# PSPS_AVNC_SRD_fullBoard-2020-09-15.net
KiCad netlist of a schematic drawn in EAGLE
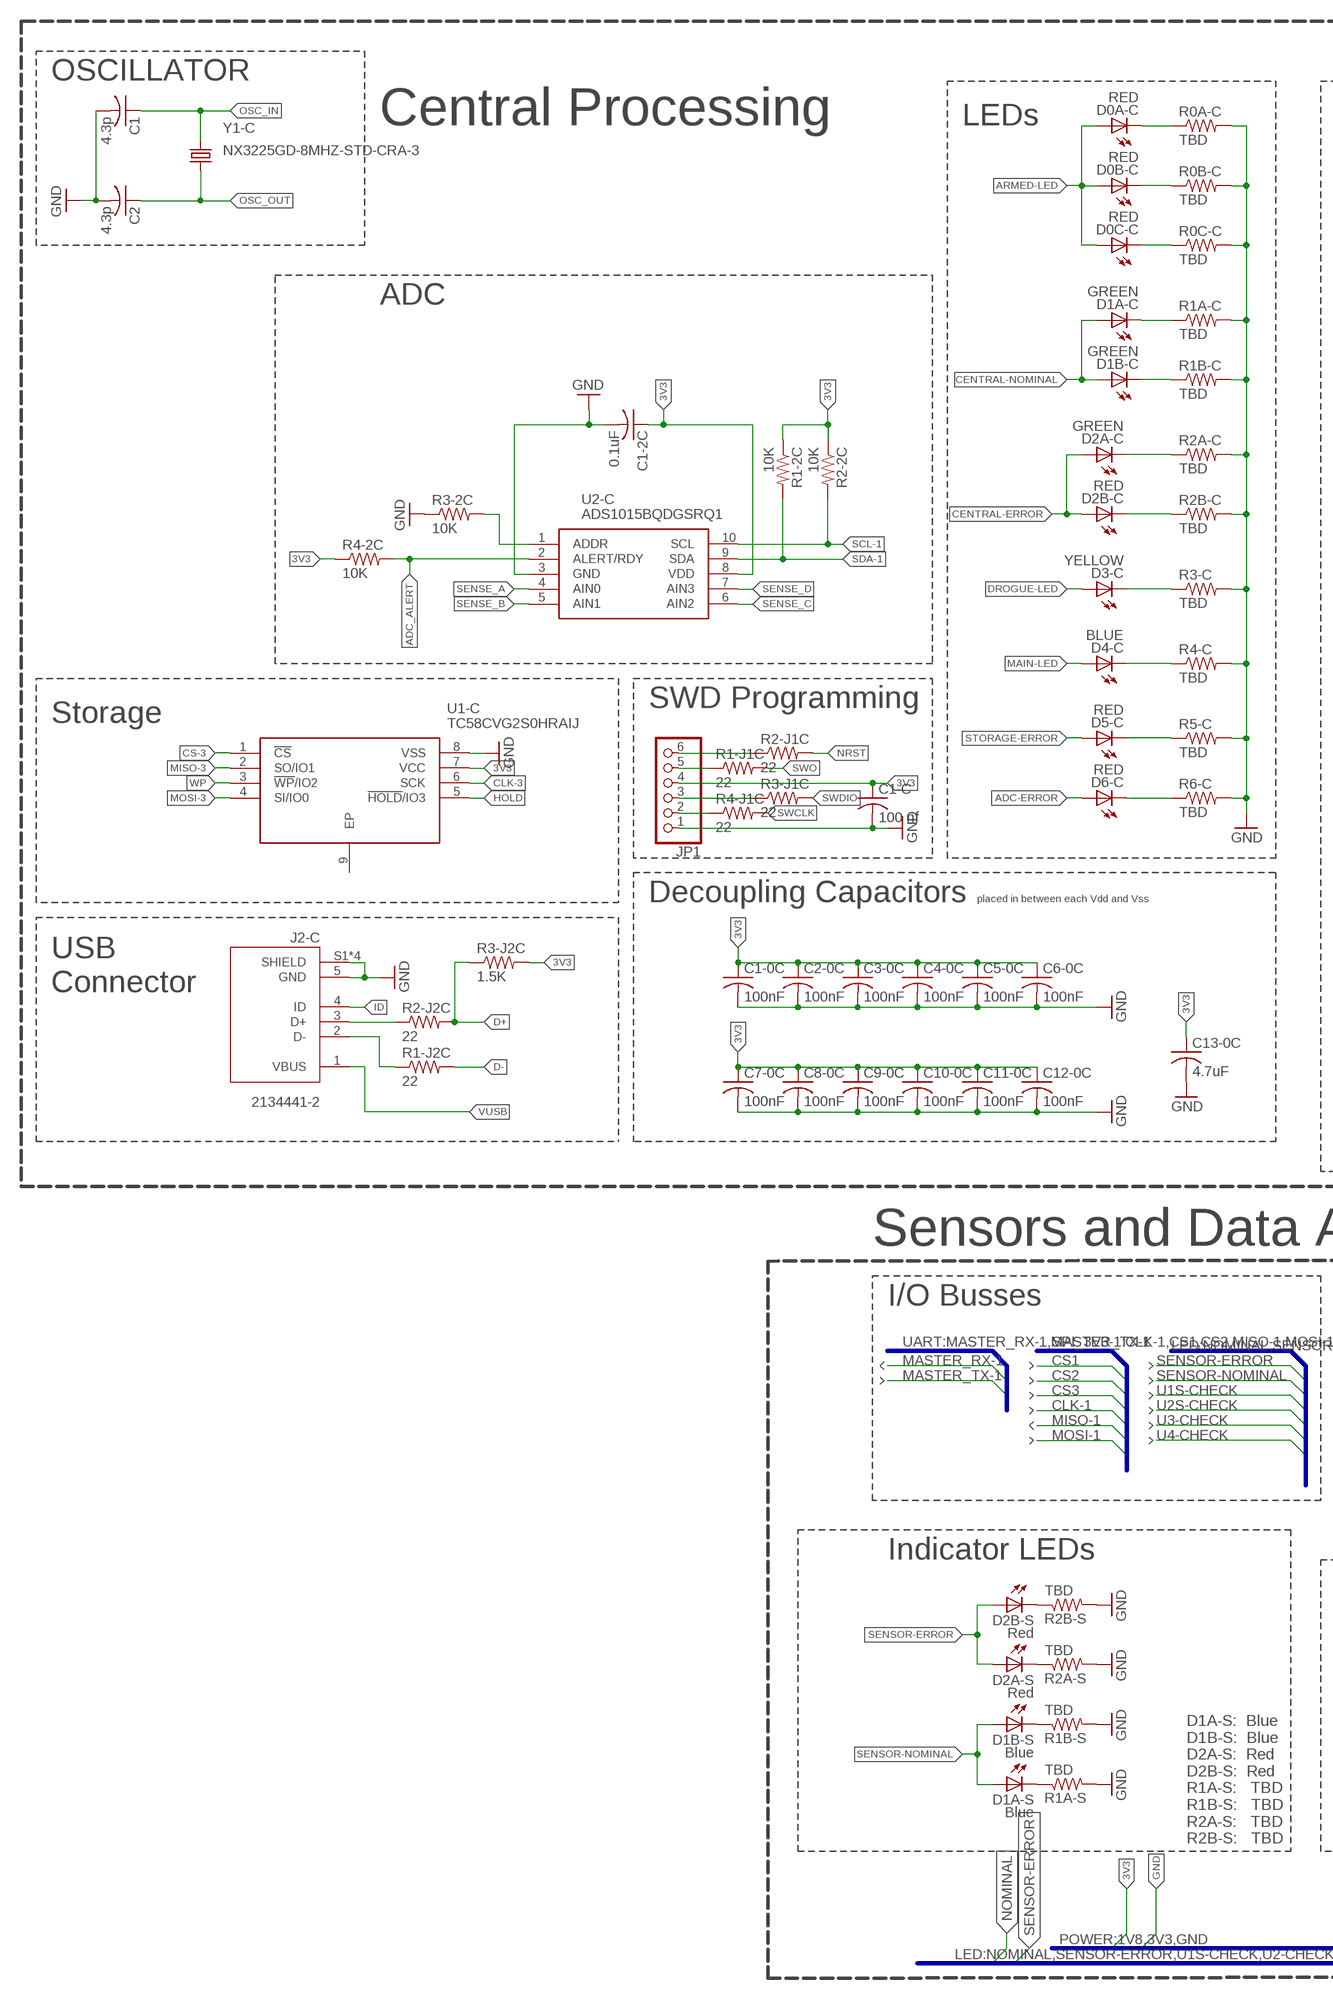
[diagram p0: schematic, sheet 1, part 1 of 3]
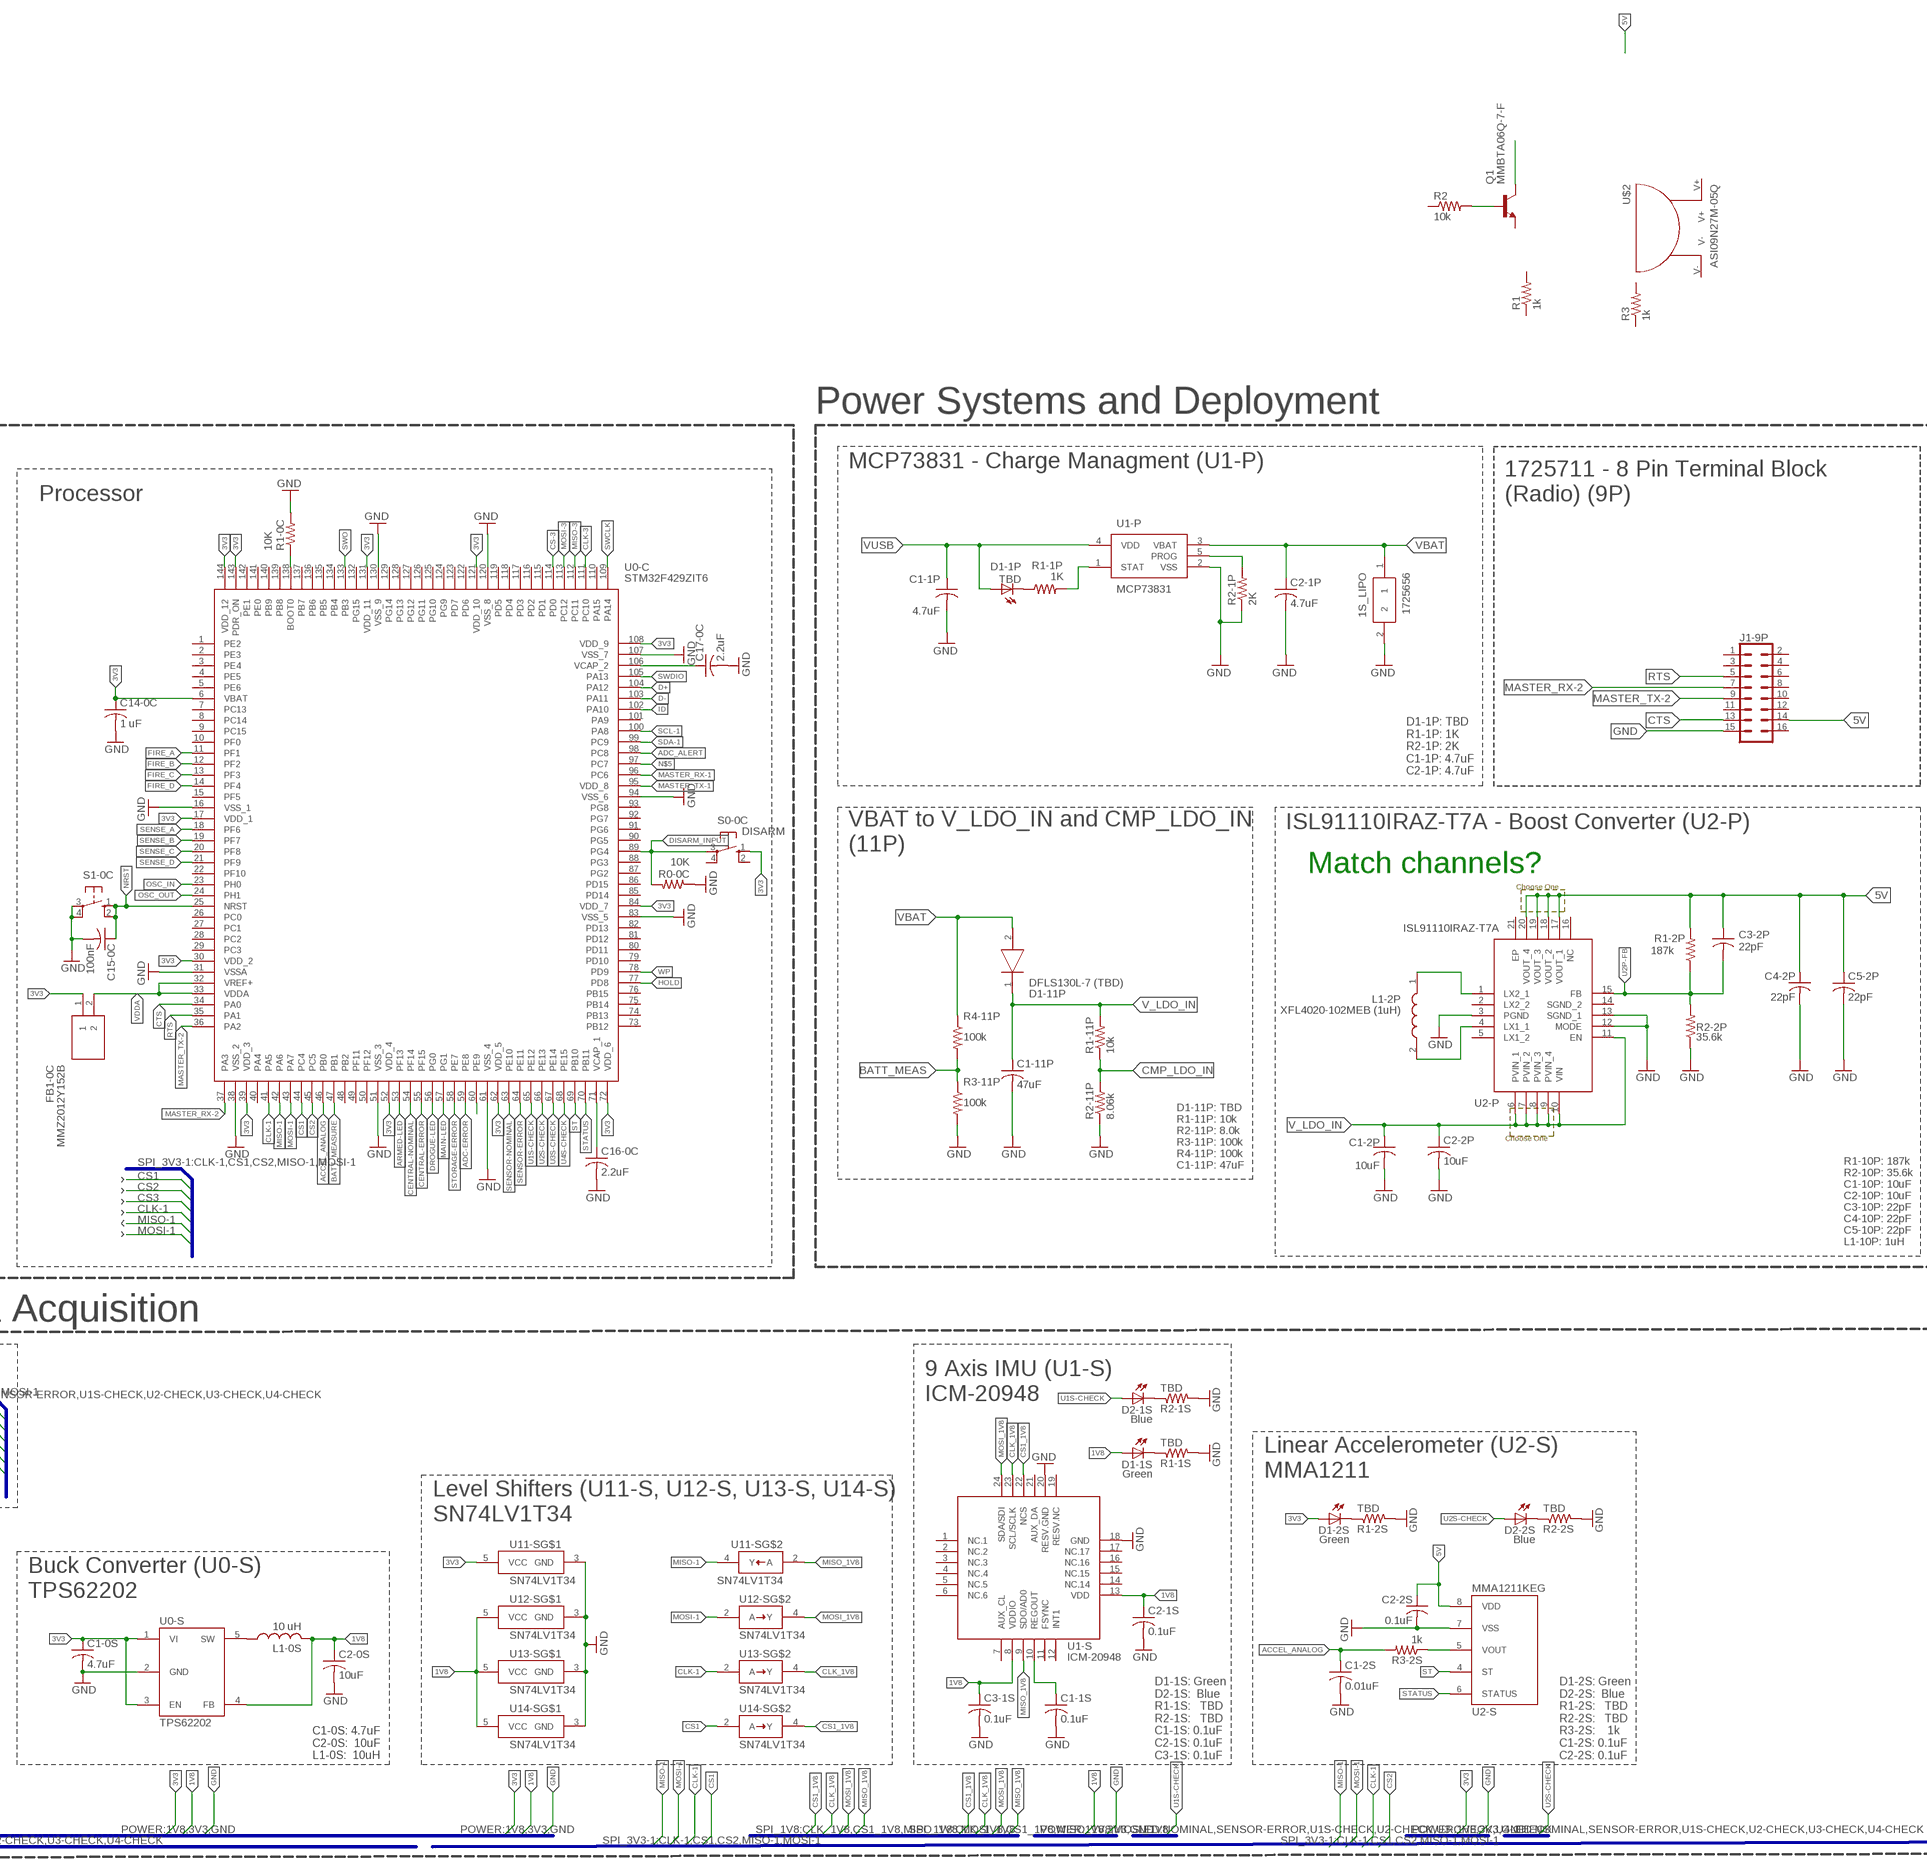
[diagram p1: schematic, sheet 1, part 2 of 3]
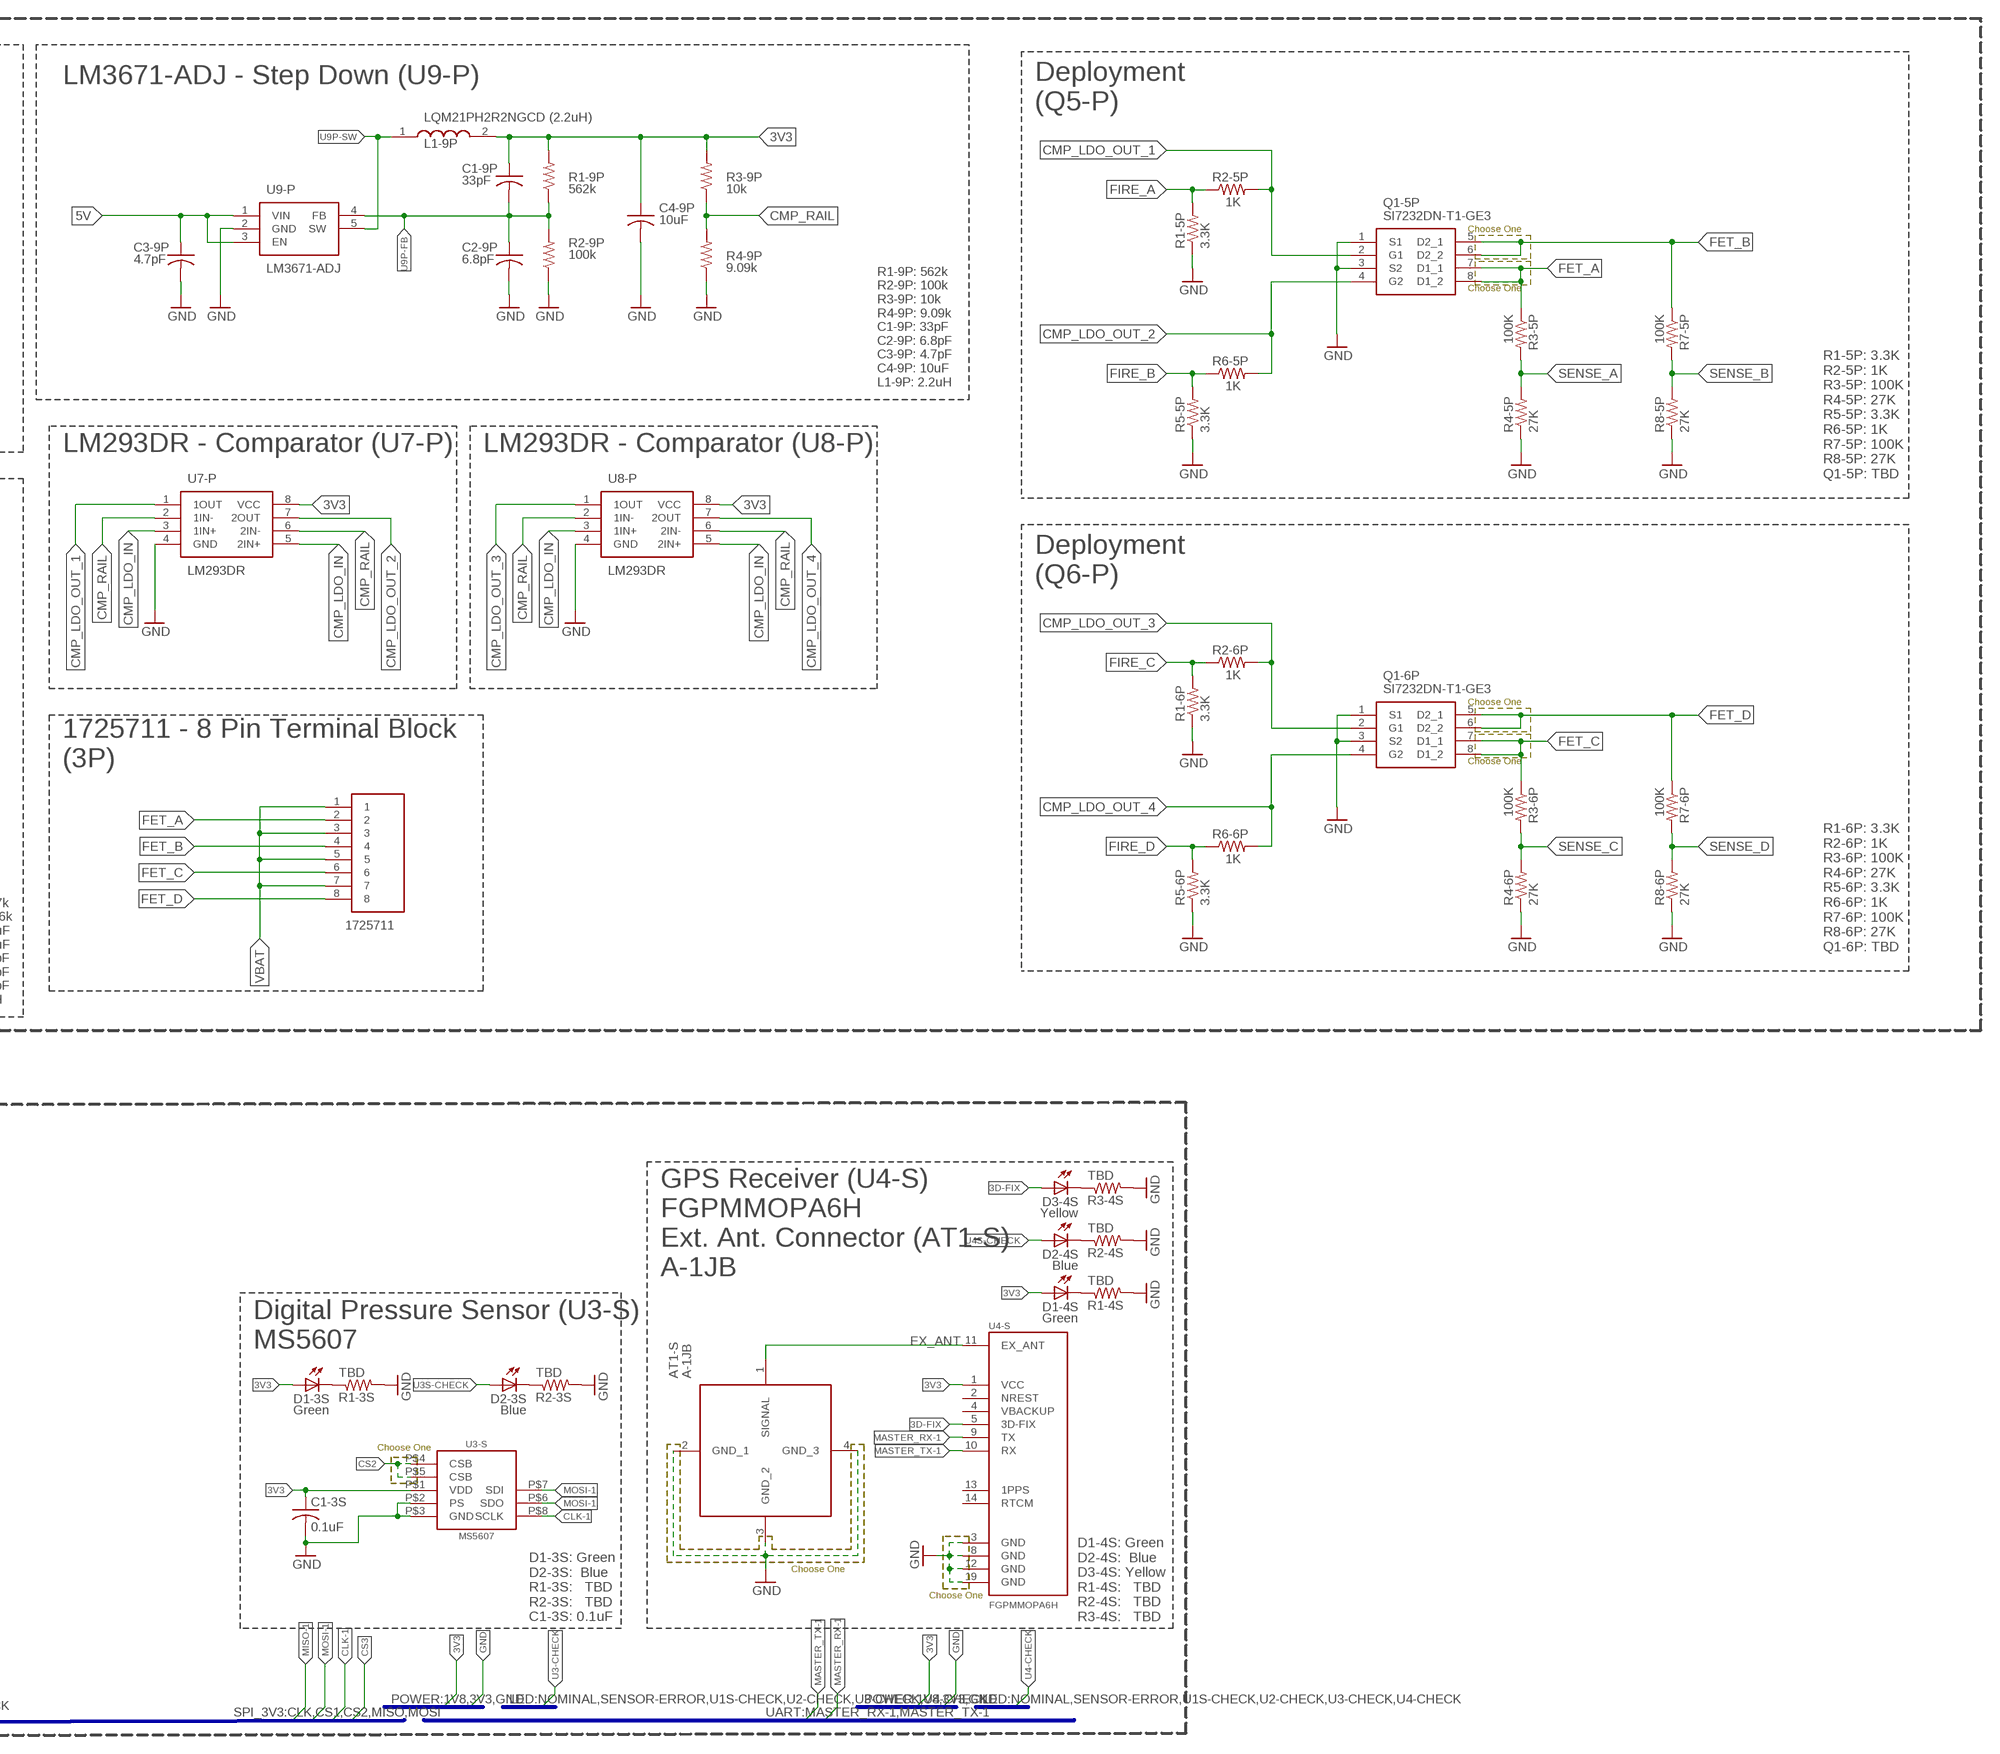
[diagram p2: schematic, sheet 1, part 3 of 3]

(export (version "E")
  (design (tool "Eeschema 10.0.6"))
  (components
    (comp (ref "1S_LIPO")
      (value "1725656")
      (footprint "eagle-import:1725656")
      (fields (field (name "MOUSER_PART_NUMBER") "651-1725656"))
      (libsource (lib "eagle-import") (part "1725656"))
    )
    (comp (ref "AT1-S")
      (value "A-1JB")
      (footprint "eagle-import:A1JB")
      (fields (field (name "MOUSER_PART_NUMBER") "523-A-1JB"))
      (libsource (lib "eagle-import") (part "A-1JB"))
    )
    (comp (ref "C1")
      (value "4.3p")
      (footprint "eagle-import:C0805")
      (libsource (lib "eagle-import") (part "rcl_334_C-USC0805"))
    )
    (comp (ref "C1-0C")
      (value "100nF")
      (footprint "eagle-import:C0805")
      (libsource (lib "eagle-import") (part "rcl_334_C-USC0805"))
    )
    (comp (ref "C1-0S")
      (value "4.7uF")
      (footprint "eagle-import:C0805")
      (libsource (lib "eagle-import") (part "resistor_348_C-USC0805"))
    )
    (comp (ref "C1-1P")
      (value "4.7uF")
      (footprint "eagle-import:C0805")
      (libsource (lib "eagle-import") (part "resistor_348_C-USC0805"))
    )
    (comp (ref "C1-1S")
      (value "0.1uF")
      (footprint "eagle-import:C0805")
      (libsource (lib "eagle-import") (part "resistor_348_C-USC0805"))
    )
    (comp (ref "C1-2C")
      (value "0.1uF")
      (footprint "eagle-import:C0805")
      (libsource (lib "eagle-import") (part "rcl_334_C-USC0805"))
    )
    (comp (ref "C1-2P")
      (value "10uF")
      (footprint "eagle-import:C0805")
      (libsource (lib "eagle-import") (part "resistor_348_C-USC0805"))
    )
    (comp (ref "C1-2S")
      (value "0.01uF")
      (footprint "eagle-import:C0805")
      (libsource (lib "eagle-import") (part "resistor_348_C-USC0805"))
    )
    (comp (ref "C1-3S")
      (value "0.1uF")
      (footprint "eagle-import:C0805")
      (libsource (lib "eagle-import") (part "resistor_348_C-USC0805"))
    )
    (comp (ref "C1-9P")
      (value "33pF")
      (footprint "eagle-import:C0805")
      (libsource (lib "eagle-import") (part "resistor_348_C-USC0805"))
    )
    (comp (ref "C1-11P")
      (value "47uF")
      (footprint "eagle-import:C0805")
      (libsource (lib "eagle-import") (part "resistor_348_C-USC0805"))
    )
    (comp (ref "C1-C")
      (value "100 nf")
      (footprint "eagle-import:C0805")
      (libsource (lib "eagle-import") (part "rcl_334_C-USC0805"))
    )
    (comp (ref "C2")
      (value "4.3p")
      (footprint "eagle-import:C0805")
      (libsource (lib "eagle-import") (part "rcl_334_C-USC0805"))
    )
    (comp (ref "C2-0C")
      (value "100nF")
      (footprint "eagle-import:C0805")
      (libsource (lib "eagle-import") (part "rcl_334_C-USC0805"))
    )
    (comp (ref "C2-0S")
      (value "10uF")
      (footprint "eagle-import:C0805")
      (libsource (lib "eagle-import") (part "resistor_348_C-USC0805"))
    )
    (comp (ref "C2-1P")
      (value "4.7uF")
      (footprint "eagle-import:C0805")
      (libsource (lib "eagle-import") (part "resistor_348_C-USC0805"))
    )
    (comp (ref "C2-1S")
      (value "0.1uF")
      (footprint "eagle-import:C0805")
      (libsource (lib "eagle-import") (part "resistor_348_C-USC0805"))
    )
    (comp (ref "C2-2P")
      (value "10uF")
      (footprint "eagle-import:C0805")
      (libsource (lib "eagle-import") (part "C-USC0805"))
    )
    (comp (ref "C2-2S")
      (value "0.1uF")
      (footprint "eagle-import:C0805")
      (libsource (lib "eagle-import") (part "resistor_348_C-USC0805"))
    )
    (comp (ref "C2-9P")
      (value "6.8pF")
      (footprint "eagle-import:C0805")
      (libsource (lib "eagle-import") (part "resistor_348_C-USC0805"))
    )
    (comp (ref "C3-0C")
      (value "100nF")
      (footprint "eagle-import:C0805")
      (libsource (lib "eagle-import") (part "rcl_334_C-USC0805"))
    )
    (comp (ref "C3-1S")
      (value "0.1uF")
      (footprint "eagle-import:C0805")
      (libsource (lib "eagle-import") (part "resistor_348_C-USC0805"))
    )
    (comp (ref "C3-2P")
      (value "22pF")
      (footprint "eagle-import:C0805")
      (libsource (lib "eagle-import") (part "resistor_348_C-USC0805"))
    )
    (comp (ref "C3-9P")
      (value "4.7pF")
      (footprint "eagle-import:C0805")
      (libsource (lib "eagle-import") (part "resistor_348_C-USC0805"))
    )
    (comp (ref "C4-0C")
      (value "100nF")
      (footprint "eagle-import:C0805")
      (libsource (lib "eagle-import") (part "rcl_334_C-USC0805"))
    )
    (comp (ref "C4-2P")
      (value "22pF")
      (footprint "eagle-import:C0805")
      (fields (field (name "SPICEPREFIX") "C"))
      (libsource (lib "eagle-import") (part "resistor_348_C-USC0805"))
    )
    (comp (ref "C4-9P")
      (value "10uF")
      (footprint "eagle-import:C0805")
      (libsource (lib "eagle-import") (part "resistor_348_C-USC0805"))
    )
    (comp (ref "C5-0C")
      (value "100nF")
      (footprint "eagle-import:C0805")
      (libsource (lib "eagle-import") (part "rcl_334_C-USC0805"))
    )
    (comp (ref "C5-2P")
      (value "22pF")
      (footprint "eagle-import:C0805")
      (libsource (lib "eagle-import") (part "C-USC0805"))
    )
    (comp (ref "C6-0C")
      (value "100nF")
      (footprint "eagle-import:C0805")
      (libsource (lib "eagle-import") (part "rcl_334_C-USC0805"))
    )
    (comp (ref "C7-0C")
      (value "100nF")
      (footprint "eagle-import:C0805")
      (libsource (lib "eagle-import") (part "rcl_334_C-USC0805"))
    )
    (comp (ref "C8-0C")
      (value "100nF")
      (footprint "eagle-import:C0805")
      (libsource (lib "eagle-import") (part "rcl_334_C-USC0805"))
    )
    (comp (ref "C9-0C")
      (value "100nF")
      (footprint "eagle-import:C0805")
      (libsource (lib "eagle-import") (part "rcl_334_C-USC0805"))
    )
    (comp (ref "C10-0C")
      (value "100nF")
      (footprint "eagle-import:C0805")
      (libsource (lib "eagle-import") (part "rcl_334_C-USC0805"))
    )
    (comp (ref "C11-0C")
      (value "100nF")
      (footprint "eagle-import:C0805")
      (libsource (lib "eagle-import") (part "rcl_334_C-USC0805"))
    )
    (comp (ref "C12-0C")
      (value "100nF")
      (footprint "eagle-import:C0805")
      (libsource (lib "eagle-import") (part "rcl_334_C-USC0805"))
    )
    (comp (ref "C13-0C")
      (value "4.7uF")
      (footprint "eagle-import:C0805")
      (libsource (lib "eagle-import") (part "rcl_334_C-USC0805"))
    )
    (comp (ref "C14-0C")
      (value "1 uF")
      (footprint "eagle-import:C0805")
      (libsource (lib "eagle-import") (part "rcl_334_C-USC0805"))
    )
    (comp (ref "C15-0C")
      (value "100nF")
      (footprint "eagle-import:C0805")
      (libsource (lib "eagle-import") (part "rcl_334_C-USC0805"))
    )
    (comp (ref "C16-0C")
      (value "2.2uF")
      (footprint "eagle-import:C0805")
      (libsource (lib "eagle-import") (part "rcl_334_C-USC0805"))
    )
    (comp (ref "C17-0C")
      (value "2.2uF")
      (footprint "eagle-import:C0805")
      (libsource (lib "eagle-import") (part "rcl_334_C-USC0805"))
    )
    (comp (ref "D0A-C")
      (value "RED")
      (footprint "eagle-import:CHIPLED_0805")
      (libsource (lib "eagle-import") (part "adafruit_420_LEDCHIPLED_0805"))
    )
    (comp (ref "D0B-C")
      (value "RED")
      (footprint "eagle-import:CHIPLED_0805")
      (libsource (lib "eagle-import") (part "adafruit_420_LEDCHIPLED_0805"))
    )
    (comp (ref "D0C-C")
      (value "RED")
      (footprint "eagle-import:CHIPLED_0805")
      (libsource (lib "eagle-import") (part "adafruit_420_LEDCHIPLED_0805"))
    )
    (comp (ref "D1-1P")
      (value "TBD")
      (footprint "eagle-import:CHIPLED_0805")
      (libsource (lib "eagle-import") (part "adafruit_420_LEDCHIPLED_0805"))
    )
    (comp (ref "D1-1S")
      (value "Green")
      (footprint "eagle-import:CHIPLED_0805")
      (libsource (lib "eagle-import") (part "LEDCHIPLED_0805"))
    )
    (comp (ref "D1-2S")
      (value "Green")
      (footprint "eagle-import:CHIPLED_0805")
      (libsource (lib "eagle-import") (part "LEDCHIPLED_0805"))
    )
    (comp (ref "D1-3S")
      (value "Green")
      (footprint "eagle-import:CHIPLED_0805")
      (libsource (lib "eagle-import") (part "LEDCHIPLED_0805"))
    )
    (comp (ref "D1-4S")
      (value "Green")
      (footprint "eagle-import:CHIPLED_0805")
      (libsource (lib "eagle-import") (part "LEDCHIPLED_0805"))
    )
    (comp (ref "D1-11P")
      (value "DFLS130L-7 (TBD)")
      (footprint "eagle-import:POWERDI_123")
      (fields
        (field (name "MANUFACTURER_PART_NUMBER") "DFLS130L-7")
        (field (name "MOUSER_PART_NUMBER") "621-DFLS130L")
      )
      (libsource (lib "eagle-import") (part "DFLS130L-7"))
    )
    (comp (ref "D1A-C")
      (value "GREEN")
      (footprint "eagle-import:CHIPLED_0805")
      (libsource (lib "eagle-import") (part "adafruit_420_LEDCHIPLED_0805"))
    )
    (comp (ref "D1A-S")
      (value "Blue")
      (footprint "eagle-import:CHIPLED_0805")
      (libsource (lib "eagle-import") (part "LEDCHIPLED_0805"))
    )
    (comp (ref "D1B-C")
      (value "GREEN")
      (footprint "eagle-import:CHIPLED_0805")
      (libsource (lib "eagle-import") (part "adafruit_420_LEDCHIPLED_0805"))
    )
    (comp (ref "D1B-S")
      (value "Blue")
      (footprint "eagle-import:CHIPLED_0805")
      (libsource (lib "eagle-import") (part "LEDCHIPLED_0805"))
    )
    (comp (ref "D2-1S")
      (value "Blue")
      (footprint "eagle-import:CHIPLED_0805")
      (libsource (lib "eagle-import") (part "LEDCHIPLED_0805"))
    )
    (comp (ref "D2-2S")
      (value "Blue")
      (footprint "eagle-import:CHIPLED_0805")
      (libsource (lib "eagle-import") (part "LEDCHIPLED_0805"))
    )
    (comp (ref "D2-3S")
      (value "Blue")
      (footprint "eagle-import:CHIPLED_0805")
      (libsource (lib "eagle-import") (part "LEDCHIPLED_0805"))
    )
    (comp (ref "D2-4S")
      (value "Blue")
      (footprint "eagle-import:CHIPLED_0805")
      (libsource (lib "eagle-import") (part "LEDCHIPLED_0805"))
    )
    (comp (ref "D2A-C")
      (value "GREEN")
      (footprint "eagle-import:CHIPLED_0805")
      (libsource (lib "eagle-import") (part "adafruit_420_LEDCHIPLED_0805"))
    )
    (comp (ref "D2A-S")
      (value "Red")
      (footprint "eagle-import:CHIPLED_0805")
      (libsource (lib "eagle-import") (part "LEDCHIPLED_0805"))
    )
    (comp (ref "D2B-C")
      (value "RED")
      (footprint "eagle-import:CHIPLED_0805")
      (libsource (lib "eagle-import") (part "adafruit_420_LEDCHIPLED_0805"))
    )
    (comp (ref "D2B-S")
      (value "Red")
      (footprint "eagle-import:CHIPLED_0805")
      (libsource (lib "eagle-import") (part "LEDCHIPLED_0805"))
    )
    (comp (ref "D3-4S")
      (value "Yellow")
      (footprint "eagle-import:CHIPLED_0805")
      (libsource (lib "eagle-import") (part "LEDCHIPLED_0805"))
    )
    (comp (ref "D3-C")
      (value "YELLOW")
      (footprint "eagle-import:CHIPLED_0805")
      (libsource (lib "eagle-import") (part "adafruit_420_LEDCHIPLED_0805"))
    )
    (comp (ref "D4-C")
      (value "BLUE")
      (footprint "eagle-import:CHIPLED_0805")
      (libsource (lib "eagle-import") (part "adafruit_420_LEDCHIPLED_0805"))
    )
    (comp (ref "D5-C")
      (value "RED")
      (footprint "eagle-import:CHIPLED_0805")
      (libsource (lib "eagle-import") (part "adafruit_420_LEDCHIPLED_0805"))
    )
    (comp (ref "D6-C")
      (value "RED")
      (footprint "eagle-import:CHIPLED_0805")
      (libsource (lib "eagle-import") (part "adafruit_420_LEDCHIPLED_0805"))
    )
    (comp (ref "FB1-0C")
      (value "MMZ2012Y152B")
      (footprint "eagle-import:BEADC2012X105N")
      (fields (field (name "MOUSER_PART_NUMBER") "810-MMZ2012Y152B"))
      (libsource (lib "eagle-import") (part "MMZ2012Y152B"))
    )
    (comp (ref "J1-9P")
      (value "CONN_08X2")
      (footprint "eagle-import:2X8")
      (libsource (lib "eagle-import") (part "CONN_08X2"))
    )
    (comp (ref "J2-C")
      (value "2134441-2")
      (footprint "eagle-import:TE_2134441-2")
      (fields (field (name "DIGI-KEY_PART_NUMBER") "A118104CT-ND") (field (name "MF") "TE Connectivity"))
      (libsource (lib "eagle-import") (part "2134441-2"))
    )
    (comp (ref "J2-CHARGETERMINAL")
      (value "1725711")
      (footprint "eagle-import:1725711")
      (fields (field (name "MOUSER_PART_NUMBER") "651-1725711"))
      (libsource (lib "eagle-import") (part "1725711"))
    )
    (comp (ref "JP1")
      (value "PINHD-1X6")
      (footprint "eagle-import:1X06")
      (libsource (lib "eagle-import") (part "PINHD-1X6"))
    )
    (comp (ref "L1-0S")
      (value "10 uH")
      (footprint "eagle-import:PF0560NL")
      (libsource (lib "eagle-import") (part "PF0560.103NLT"))
    )
    (comp (ref "L1-2P")
      (value "XFL4020-102MEB (1uH)")
      (footprint "eagle-import:XFL4020")
      (fields
        (field (name "MANUFACTURER_PART_NUMBER") "XFL4020-102MEB")
        (field (name "MOUSER_PART_NUMBER") "994-XFL4020-102MEB")
      )
      (libsource (lib "eagle-import") (part "XFL4020-102MEB"))
    )
    (comp (ref "L1-9P")
      (value "LQM21PH2R2NGCD (2.2uH)")
      (footprint "eagle-import:INDC2012X100N")
      (fields
        (field (name "MANUFACTURER_PART_NUMBER") "LQM21PH2R2NGCD")
        (field (name "MOUSER_PART_NUMBER") "81-LQM21PH2R2NGCD")
      )
      (libsource (lib "eagle-import") (part "LQM21PH2R2NGCD"))
    )
    (comp (ref "Q1")
      (value "MMBTA06Q-7-F")
      (footprint "eagle-import:SOT23")
      (libsource (lib "eagle-import") (part "NPN_TRANSISTOR"))
    )
    (comp (ref "Q1-5P")
      (value "SI7232DN-T1-GE3")
      (footprint "eagle-import:POWERPAK-1212-8")
      (fields (field (name "MOUSER_PART_NUMBER") "781-SI7232DN-GE3"))
      (libsource (lib "eagle-import") (part "SI7232DN-T1-GE3"))
    )
    (comp (ref "Q1-6P")
      (value "SI7232DN-T1-GE3")
      (footprint "eagle-import:POWERPAK-1212-8")
      (fields (field (name "MOUSER_PART_NUMBER") "781-SI7232DN-GE3"))
      (libsource (lib "eagle-import") (part "SI7232DN-T1-GE3"))
    )
    (comp (ref "R0-0C")
      (value "10K")
      (footprint "eagle-import:R0805")
      (libsource (lib "eagle-import") (part "rcl_334_R-US_R0805"))
    )
    (comp (ref "R0A-C")
      (value "TBD")
      (footprint "eagle-import:M0805")
      (libsource (lib "eagle-import") (part "rcl_334_R-US_M0805"))
    )
    (comp (ref "R0B-C")
      (value "TBD")
      (footprint "eagle-import:M0805")
      (libsource (lib "eagle-import") (part "rcl_334_R-US_M0805"))
    )
    (comp (ref "R0C-C")
      (value "TBD")
      (footprint "eagle-import:M0805")
      (libsource (lib "eagle-import") (part "rcl_334_R-US_M0805"))
    )
    (comp (ref "R1")
      (value "1k")
      (footprint "eagle-import:R0805")
      (libsource (lib "eagle-import") (part "resistor_348_R-US_R0805"))
    )
    (comp (ref "R1-0C")
      (value "10K")
      (footprint "eagle-import:R0805")
      (libsource (lib "eagle-import") (part "rcl_334_R-US_R0805"))
    )
    (comp (ref "R1-1P")
      (value "1K")
      (footprint "eagle-import:R0805")
      (libsource (lib "eagle-import") (part "resistor_348_R-US_R0805"))
    )
    (comp (ref "R1-1S")
      (value "TBD")
      (footprint "eagle-import:R0805")
      (libsource (lib "eagle-import") (part "resistor_348_R-US_R0805"))
    )
    (comp (ref "R1-2C")
      (value "10K")
      (footprint "eagle-import:R0805")
      (libsource (lib "eagle-import") (part "rcl_334_R-US_R0805"))
    )
    (comp (ref "R1-2P")
      (value "187k")
      (footprint "eagle-import:R0805")
      (libsource (lib "eagle-import") (part "resistor_348_R-US_R0805"))
    )
    (comp (ref "R1-2S")
      (value "TBD")
      (footprint "eagle-import:R0805")
      (libsource (lib "eagle-import") (part "resistor_348_R-US_R0805"))
    )
    (comp (ref "R1-3S")
      (value "TBD")
      (footprint "eagle-import:R0805")
      (libsource (lib "eagle-import") (part "resistor_348_R-US_R0805"))
    )
    (comp (ref "R1-4S")
      (value "TBD")
      (footprint "eagle-import:R0805")
      (libsource (lib "eagle-import") (part "resistor_348_R-US_R0805"))
    )
    (comp (ref "R1-5P")
      (value "3.3K")
      (footprint "eagle-import:M0805")
      (libsource (lib "eagle-import") (part "rcl_334_R-US_M0805"))
    )
    (comp (ref "R1-6P")
      (value "3.3K")
      (footprint "eagle-import:M0805")
      (libsource (lib "eagle-import") (part "rcl_334_R-US_M0805"))
    )
    (comp (ref "R1-9P")
      (value "562k")
      (footprint "eagle-import:R0805")
      (libsource (lib "eagle-import") (part "resistor_348_R-US_R0805"))
    )
    (comp (ref "R1-11P")
      (value "10k")
      (footprint "eagle-import:R0805")
      (libsource (lib "eagle-import") (part "resistor_348_R-US_R0805"))
    )
    (comp (ref "R1-J1C")
      (value "22")
      (footprint "eagle-import:M0805")
      (libsource (lib "eagle-import") (part "rcl_334_R-US_M0805"))
    )
    (comp (ref "R1-J2C")
      (value "22")
      (footprint "eagle-import:M0805")
      (libsource (lib "eagle-import") (part "rcl_334_R-US_M0805"))
    )
    (comp (ref "R1A-C")
      (value "TBD")
      (footprint "eagle-import:M0805")
      (libsource (lib "eagle-import") (part "rcl_334_R-US_M0805"))
    )
    (comp (ref "R1A-S")
      (value "TBD")
      (footprint "eagle-import:R0805")
      (libsource (lib "eagle-import") (part "resistor_348_R-US_R0805"))
    )
    (comp (ref "R1B-C")
      (value "TBD")
      (footprint "eagle-import:M0805")
      (libsource (lib "eagle-import") (part "rcl_334_R-US_M0805"))
    )
    (comp (ref "R1B-S")
      (value "TBD")
      (footprint "eagle-import:R0805")
      (libsource (lib "eagle-import") (part "resistor_348_R-US_R0805"))
    )
    (comp (ref "R2")
      (value "10k")
      (footprint "eagle-import:R0805")
      (libsource (lib "eagle-import") (part "resistor_348_R-US_R0805"))
    )
    (comp (ref "R2-1P")
      (value "2K")
      (footprint "eagle-import:R0805")
      (libsource (lib "eagle-import") (part "resistor_348_R-US_R0805"))
    )
    (comp (ref "R2-1S")
      (value "TBD")
      (footprint "eagle-import:R0805")
      (libsource (lib "eagle-import") (part "resistor_348_R-US_R0805"))
    )
    (comp (ref "R2-2C")
      (value "10K")
      (footprint "eagle-import:R0805")
      (libsource (lib "eagle-import") (part "rcl_334_R-US_R0805"))
    )
    (comp (ref "R2-2P")
      (value "35.6k")
      (footprint "eagle-import:R0805")
      (libsource (lib "eagle-import") (part "resistor_348_R-US_R0805"))
    )
    (comp (ref "R2-2S")
      (value "TBD")
      (footprint "eagle-import:R0805")
      (libsource (lib "eagle-import") (part "resistor_348_R-US_R0805"))
    )
    (comp (ref "R2-3S")
      (value "TBD")
      (footprint "eagle-import:R0805")
      (libsource (lib "eagle-import") (part "resistor_348_R-US_R0805"))
    )
    (comp (ref "R2-4S")
      (value "TBD")
      (footprint "eagle-import:R0805")
      (libsource (lib "eagle-import") (part "resistor_348_R-US_R0805"))
    )
    (comp (ref "R2-5P")
      (value "1K")
      (footprint "eagle-import:M0805")
      (libsource (lib "eagle-import") (part "rcl_334_R-US_M0805"))
    )
    (comp (ref "R2-6P")
      (value "1K")
      (footprint "eagle-import:M0805")
      (libsource (lib "eagle-import") (part "rcl_334_R-US_M0805"))
    )
    (comp (ref "R2-9P")
      (value "100k")
      (footprint "eagle-import:R0805")
      (libsource (lib "eagle-import") (part "resistor_348_R-US_R0805"))
    )
    (comp (ref "R2-11P")
      (value "8.06k")
      (footprint "eagle-import:R0805")
      (libsource (lib "eagle-import") (part "resistor_348_R-US_R0805"))
    )
    (comp (ref "R2-J1C")
      (value "22")
      (footprint "eagle-import:M0805")
      (libsource (lib "eagle-import") (part "rcl_334_R-US_M0805"))
    )
    (comp (ref "R2-J2C")
      (value "22")
      (footprint "eagle-import:M0805")
      (libsource (lib "eagle-import") (part "rcl_334_R-US_M0805"))
    )
    (comp (ref "R2A-C")
      (value "TBD")
      (footprint "eagle-import:M0805")
      (libsource (lib "eagle-import") (part "rcl_334_R-US_M0805"))
    )
    (comp (ref "R2A-S")
      (value "TBD")
      (footprint "eagle-import:R0805")
      (libsource (lib "eagle-import") (part "resistor_348_R-US_R0805"))
    )
    (comp (ref "R2B-C")
      (value "TBD")
      (footprint "eagle-import:M0805")
      (libsource (lib "eagle-import") (part "rcl_334_R-US_M0805"))
    )
    (comp (ref "R2B-S")
      (value "TBD")
      (footprint "eagle-import:R0805")
      (libsource (lib "eagle-import") (part "resistor_348_R-US_R0805"))
    )
    (comp (ref "R3")
      (value "1k")
      (footprint "eagle-import:R0805")
      (libsource (lib "eagle-import") (part "resistor_348_R-US_R0805"))
    )
    (comp (ref "R3-2C")
      (value "10K")
      (footprint "eagle-import:R0805")
      (libsource (lib "eagle-import") (part "rcl_334_R-US_R0805"))
    )
    (comp (ref "R3-2S")
      (value "1k")
      (footprint "eagle-import:R0805")
      (libsource (lib "eagle-import") (part "resistor_348_R-US_R0805"))
    )
    (comp (ref "R3-4S")
      (value "TBD")
      (footprint "eagle-import:R0805")
      (libsource (lib "eagle-import") (part "resistor_348_R-US_R0805"))
    )
    (comp (ref "R3-5P")
      (value "100K")
      (footprint "eagle-import:M0805")
      (libsource (lib "eagle-import") (part "rcl_334_R-US_M0805"))
    )
    (comp (ref "R3-6P")
      (value "100K")
      (footprint "eagle-import:M0805")
      (libsource (lib "eagle-import") (part "rcl_334_R-US_M0805"))
    )
    (comp (ref "R3-9P")
      (value "10k")
      (footprint "eagle-import:R0805")
      (libsource (lib "eagle-import") (part "resistor_348_R-US_R0805"))
    )
    (comp (ref "R3-11P")
      (value "100k")
      (footprint "eagle-import:R0805")
      (libsource (lib "eagle-import") (part "R-US_R0805"))
    )
    (comp (ref "R3-C")
      (value "TBD")
      (footprint "eagle-import:M0805")
      (libsource (lib "eagle-import") (part "rcl_334_R-US_M0805"))
    )
    (comp (ref "R3-J1C")
      (value "22")
      (footprint "eagle-import:M0805")
      (libsource (lib "eagle-import") (part "rcl_334_R-US_M0805"))
    )
    (comp (ref "R3-J2C")
      (value "1.5K")
      (footprint "eagle-import:M0805")
      (libsource (lib "eagle-import") (part "rcl_334_R-US_M0805"))
    )
    (comp (ref "R4-2C")
      (value "10K")
      (footprint "eagle-import:R0805")
      (libsource (lib "eagle-import") (part "rcl_334_R-US_R0805"))
    )
    (comp (ref "R4-5P")
      (value "27K")
      (footprint "eagle-import:M0805")
      (libsource (lib "eagle-import") (part "rcl_334_R-US_M0805"))
    )
    (comp (ref "R4-6P")
      (value "27K")
      (footprint "eagle-import:M0805")
      (libsource (lib "eagle-import") (part "rcl_334_R-US_M0805"))
    )
    (comp (ref "R4-9P")
      (value "9.09k")
      (footprint "eagle-import:R0805")
      (libsource (lib "eagle-import") (part "resistor_348_R-US_R0805"))
    )
    (comp (ref "R4-11P")
      (value "100k")
      (footprint "eagle-import:R0805")
      (libsource (lib "eagle-import") (part "R-US_R0805"))
    )
    (comp (ref "R4-C")
      (value "TBD")
      (footprint "eagle-import:M0805")
      (libsource (lib "eagle-import") (part "rcl_334_R-US_M0805"))
    )
    (comp (ref "R4-J1C")
      (value "22")
      (footprint "eagle-import:M0805")
      (libsource (lib "eagle-import") (part "rcl_334_R-US_M0805"))
    )
    (comp (ref "R5-5P")
      (value "3.3K")
      (footprint "eagle-import:M0805")
      (libsource (lib "eagle-import") (part "rcl_334_R-US_M0805"))
    )
    (comp (ref "R5-6P")
      (value "3.3K")
      (footprint "eagle-import:M0805")
      (libsource (lib "eagle-import") (part "rcl_334_R-US_M0805"))
    )
    (comp (ref "R5-C")
      (value "TBD")
      (footprint "eagle-import:M0805")
      (libsource (lib "eagle-import") (part "rcl_334_R-US_M0805"))
    )
    (comp (ref "R6-5P")
      (value "1K")
      (footprint "eagle-import:M0805")
      (libsource (lib "eagle-import") (part "rcl_334_R-US_M0805"))
    )
    (comp (ref "R6-6P")
      (value "1K")
      (footprint "eagle-import:M0805")
      (libsource (lib "eagle-import") (part "rcl_334_R-US_M0805"))
    )
    (comp (ref "R6-C")
      (value "TBD")
      (footprint "eagle-import:M0805")
      (libsource (lib "eagle-import") (part "rcl_334_R-US_M0805"))
    )
    (comp (ref "R7-5P")
      (value "100K")
      (footprint "eagle-import:M0805")
      (libsource (lib "eagle-import") (part "rcl_334_R-US_M0805"))
    )
    (comp (ref "R7-6P")
      (value "100K")
      (footprint "eagle-import:M0805")
      (libsource (lib "eagle-import") (part "rcl_334_R-US_M0805"))
    )
    (comp (ref "R8-5P")
      (value "27K")
      (footprint "eagle-import:M0805")
      (libsource (lib "eagle-import") (part "rcl_334_R-US_M0805"))
    )
    (comp (ref "R8-6P")
      (value "27K")
      (footprint "eagle-import:M0805")
      (libsource (lib "eagle-import") (part "rcl_334_R-US_M0805"))
    )
    (comp (ref "S0-0C")
      (value "DISARM")
      (footprint "eagle-import:B3F-10XX")
      (fields (field (name "MPN") "B3F-1000"))
      (libsource (lib "eagle-import") (part "10-XX"))
    )
    (comp (ref "S1-0C")
      (value "10-XX")
      (footprint "eagle-import:B3F-10XX")
      (fields (field (name "MPN") "B3F-1000"))
      (libsource (lib "eagle-import") (part "10-XX"))
    )
    (comp (ref "U$2")
      (value "ASI09N27M-05Q")
      (footprint "eagle-import:ASI09N27M-05Q")
      (libsource (lib "eagle-import") (part "ASI09N27M-05Q"))
    )
    (comp (ref "U0-C")
      (value "STM32F429ZIT6")
      (footprint "eagle-import:QFP50P2200X2200X160-144N")
      (fields (field (name "MOUSER_PART_NUMBER") "511-STM32F429ZIT6"))
      (libsource (lib "eagle-import") (part "STM32F429ZIT6"))
    )
    (comp (ref "U0-S")
      (value "TPS62202")
      (footprint "eagle-import:SOT95P280X145-5")
      (libsource (lib "eagle-import") (part "TPS62202"))
    )
    (comp (ref "U1-C")
      (value "TC58CVG2S0HRAIJ")
      (footprint "eagle-import:SON127P800X600X80-9N")
      (fields (field (name "MOUSER_PART_NUMBER") "757-TC58CVG2S0HRAIJ"))
      (libsource (lib "eagle-import") (part "TC58CVG2S0HRAIJ"))
    )
    (comp (ref "U1-P")
      (value "MCP73831")
      (footprint "eagle-import:SOT95P270X145-5N")
      (fields
        (field (name "MANUFACTURER_PART_NUMBER") "MCP73831T-2ACI/OT")
        (field (name "MOUSER_PART_NUMBER") "579-MCP73831T-2ACIOT")
      )
      (libsource (lib "eagle-import") (part "MCP73831T-2ACI_OT"))
    )
    (comp (ref "U1-S")
      (value "ICM-20948")
      (footprint "eagle-import:QFN40P300X300X105-25T159X175")
      (libsource (lib "eagle-import") (part "ICM-20948"))
    )
    (comp (ref "U2-C")
      (value "ADS1015BQDGSRQ1")
      (footprint "eagle-import:SOP50P490X110-10N")
      (fields (field (name "MOUSER_PART_NUMBER") "595-ADS1015BQDGSRQ1"))
      (libsource (lib "eagle-import") (part "ADS1015BQDGSRQ1"))
    )
    (comp (ref "U2-P")
      (value "ISL91110IRAZ-T7A")
      (footprint "eagle-import:QFN50P400X400X100-21N")
      (libsource (lib "eagle-import") (part "ISL91110IRAZ-T7A"))
    )
    (comp (ref "U2-S")
      (value "MMA1211KEG")
      (footprint "eagle-import:SOIC127P1041X355-16N")
      (libsource (lib "eagle-import") (part "MMA1211KEG"))
    )
    (comp (ref "U3-S")
      (value "MS5607")
      (footprint "eagle-import:MS5607")
      (libsource (lib "eagle-import") (part "MS5607"))
    )
    (comp (ref "U4-S")
      (value "FGPMMOPA6H")
      (footprint "eagle-import:SOIC127P1800X470-20N")
      (libsource (lib "eagle-import") (part "FGPMMOPA6H"))
    )
    (comp (ref "U7-P")
      (value "LM293DR")
      (footprint "eagle-import:SOIC127P600X175-8N")
      (fields (field (name "MOUSER_PART_NUMBER") "595-LM293DR"))
      (libsource (lib "eagle-import") (part "LM293DR"))
    )
    (comp (ref "U8-P")
      (value "LM293DR")
      (footprint "eagle-import:SOIC127P600X175-8N")
      (fields (field (name "MOUSER_PART_NUMBER") "595-LM293DR"))
      (libsource (lib "eagle-import") (part "LM293DR"))
    )
    (comp (ref "U9-P")
      (value "LM3671-ADJ")
      (footprint "eagle-import:SOT95P280X145-5N")
      (fields
        (field (name "MANUFACTURER_PART_NUMBER") "LM3671MFX-ADJ/NOPB")
        (field (name "MOUSER_PART_NUMBER") "926-LM3671MFXADJNOPB")
      )
      (libsource (lib "eagle-import") (part "LM3671MFX-ADJ_NOPB"))
    )
    (comp (ref "U11-S")
      (value "SN74LV1T34")
      (footprint "eagle-import:SOT65P210X110-5")
      (libsource (lib "eagle-import") (part "SN74LV1T34"))
    )
    (comp (ref "U12-S")
      (value "SN74LV1T34")
      (footprint "eagle-import:SOT65P210X110-5")
      (libsource (lib "eagle-import") (part "SN74LV1T34"))
    )
    (comp (ref "U13-S")
      (value "SN74LV1T34")
      (footprint "eagle-import:SOT65P210X110-5")
      (libsource (lib "eagle-import") (part "SN74LV1T34"))
    )
    (comp (ref "U14-S")
      (value "SN74LV1T34")
      (footprint "eagle-import:SOT65P210X110-5")
      (libsource (lib "eagle-import") (part "SN74LV1T34"))
    )
    (comp (ref "Y1-C")
      (value "NX3225GD-8MHZ-STD-CRA-3")
      (footprint "eagle-import:3.2X2.5_KX-7")
      (libsource (lib "eagle-import") (part "KX-7"))
    )
  )
  (nets
    (net (code "10") (name "/EX_ANT") (class "Default")
      (node (ref "AT1-S") (pin "1") (pinfunction "SIGNAL_1") (pintype "bidirectional"))
      (node (ref "U4-S") (pin "11") (pinfunction "EX_ANT_11") (pintype "bidirectional"))
    )
    (net (code "17") (name "1V8") (class "Default")
      (node (ref "C2-0S") (pin "1") (pinfunction "1_1") (pintype "passive"))
      (node (ref "C2-1S") (pin "1") (pinfunction "1_1") (pintype "passive"))
      (node (ref "C3-1S") (pin "1") (pinfunction "1_1") (pintype "passive"))
      (node (ref "D1-1S") (pin "A") (pinfunction "A_A") (pintype "passive"))
      (node (ref "L1-0S") (pin "P$2") (pinfunction "2_P$2") (pintype "passive"))
      (node (ref "U0-S") (pin "4") (pinfunction "FB_4") (pintype "bidirectional"))
      (node (ref "U1-S") (pin "13") (pinfunction "VDD_13") (pintype "bidirectional"))
      (node (ref "U1-S") (pin "8") (pinfunction "VDDIO_8") (pintype "bidirectional"))
      (node (ref "U12-S") (pin "5") (pinfunction "VCC_5") (pintype "bidirectional"))
      (node (ref "U13-S") (pin "5") (pinfunction "VCC_5") (pintype "bidirectional"))
      (node (ref "U14-S") (pin "5") (pinfunction "VCC_5") (pintype "bidirectional"))
    )
    (net (code "18") (name "3D-FIX") (class "Default")
      (node (ref "D3-4S") (pin "A") (pinfunction "A_A") (pintype "passive"))
      (node (ref "U4-S") (pin "5") (pinfunction "3D-FIX_5") (pintype "bidirectional"))
    )
    (net (code "19") (name "3V3") (class "Default")
      (node (ref "C1-0C") (pin "1") (pinfunction "1_1") (pintype "passive"))
      (node (ref "C1-0S") (pin "1") (pinfunction "1_1") (pintype "passive"))
      (node (ref "C1-2C") (pin "1") (pinfunction "1_1") (pintype "passive"))
      (node (ref "C1-3S") (pin "1") (pinfunction "1_1") (pintype "passive"))
      (node (ref "C1-9P") (pin "1") (pinfunction "1_1") (pintype "passive"))
      (node (ref "C1-C") (pin "1") (pinfunction "1_1") (pintype "passive"))
      (node (ref "C10-0C") (pin "1") (pinfunction "1_1") (pintype "passive"))
      (node (ref "C11-0C") (pin "1") (pinfunction "1_1") (pintype "passive"))
      (node (ref "C12-0C") (pin "1") (pinfunction "1_1") (pintype "passive"))
      (node (ref "C13-0C") (pin "1") (pinfunction "1_1") (pintype "passive"))
      (node (ref "C14-0C") (pin "1") (pinfunction "1_1") (pintype "passive"))
      (node (ref "C2-0C") (pin "1") (pinfunction "1_1") (pintype "passive"))
      (node (ref "C3-0C") (pin "1") (pinfunction "1_1") (pintype "passive"))
      (node (ref "C4-0C") (pin "1") (pinfunction "1_1") (pintype "passive"))
      (node (ref "C4-9P") (pin "1") (pinfunction "1_1") (pintype "passive"))
      (node (ref "C5-0C") (pin "1") (pinfunction "1_1") (pintype "passive"))
      (node (ref "C6-0C") (pin "1") (pinfunction "1_1") (pintype "passive"))
      (node (ref "C7-0C") (pin "1") (pinfunction "1_1") (pintype "passive"))
      (node (ref "C8-0C") (pin "1") (pinfunction "1_1") (pintype "passive"))
      (node (ref "C9-0C") (pin "1") (pinfunction "1_1") (pintype "passive"))
      (node (ref "D1-2S") (pin "A") (pinfunction "A_A") (pintype "passive"))
      (node (ref "D1-3S") (pin "A") (pinfunction "A_A") (pintype "passive"))
      (node (ref "D1-4S") (pin "A") (pinfunction "A_A") (pintype "passive"))
      (node (ref "FB1-0C") (pin "1") (pinfunction "1_1") (pintype "bidirectional"))
      (node (ref "JP1") (pin "4") (pinfunction "4_4") (pintype "passive"))
      (node (ref "L1-9P") (pin "2") (pinfunction "2_2") (pintype "bidirectional"))
      (node (ref "R1-2C") (pin "1") (pinfunction "1_1") (pintype "passive"))
      (node (ref "R1-9P") (pin "2") (pinfunction "2_2") (pintype "passive"))
      (node (ref "R2-2C") (pin "1") (pinfunction "1_1") (pintype "passive"))
      (node (ref "R3-9P") (pin "2") (pinfunction "2_2") (pintype "passive"))
      (node (ref "R3-J2C") (pin "2") (pinfunction "2_2") (pintype "passive"))
      (node (ref "R4-2C") (pin "1") (pinfunction "1_1") (pintype "passive"))
      (node (ref "S0-0C") (pin "1") (pinfunction "S_1") (pintype "passive"))
      (node (ref "U0-C") (pin "108") (pinfunction "VDD_9_108") (pintype "power_in"))
      (node (ref "U0-C") (pin "121") (pinfunction "VDD_10_121") (pintype "power_in"))
      (node (ref "U0-C") (pin "131") (pinfunction "VDD_11_131") (pintype "power_in"))
      (node (ref "U0-C") (pin "143") (pinfunction "PDR_ON_143") (pintype "bidirectional"))
      (node (ref "U0-C") (pin "144") (pinfunction "VDD_12_144") (pintype "power_in"))
      (node (ref "U0-C") (pin "17") (pinfunction "VDD_1_17") (pintype "power_in"))
      (node (ref "U0-C") (pin "30") (pinfunction "VDD_2_30") (pintype "power_in"))
      (node (ref "U0-C") (pin "39") (pinfunction "VDD_3_39") (pintype "power_in"))
      (node (ref "U0-C") (pin "52") (pinfunction "VDD_4_52") (pintype "power_in"))
      (node (ref "U0-C") (pin "6") (pinfunction "VBAT_6") (pintype "bidirectional"))
      (node (ref "U0-C") (pin "62") (pinfunction "VDD_5_62") (pintype "power_in"))
      (node (ref "U0-C") (pin "72") (pinfunction "VDD_6_72") (pintype "power_in"))
      (node (ref "U0-C") (pin "84") (pinfunction "VDD_7_84") (pintype "power_in"))
      (node (ref "U0-S") (pin "1") (pinfunction "VI_1") (pintype "bidirectional"))
      (node (ref "U0-S") (pin "3") (pinfunction "EN_3") (pintype "bidirectional"))
      (node (ref "U1-C") (pin "7") (pinfunction "VCC_7") (pintype "bidirectional"))
      (node (ref "U11-S") (pin "5") (pinfunction "VCC_5") (pintype "bidirectional"))
      (node (ref "U2-C") (pin "8") (pinfunction "VDD_8") (pintype "bidirectional"))
      (node (ref "U3-S") (pin "P$1") (pinfunction "VDD_P$1") (pintype "bidirectional"))
      (node (ref "U4-S") (pin "1") (pinfunction "VCC_1") (pintype "bidirectional"))
      (node (ref "U7-P") (pin "8") (pinfunction "VCC_8") (pintype "bidirectional"))
      (node (ref "U8-P") (pin "8") (pinfunction "VCC_8") (pintype "bidirectional"))
    )
    (net (code "20") (name "5V") (class "Default")
      (node (ref "C2-2S") (pin "1") (pinfunction "1_1") (pintype "passive"))
      (node (ref "C3-2P") (pin "1") (pinfunction "1_1") (pintype "passive"))
      (node (ref "C3-9P") (pin "1") (pinfunction "1_1") (pintype "passive"))
      (node (ref "C4-2P") (pin "1") (pinfunction "1_1") (pintype "passive"))
      (node (ref "C5-2P") (pin "1") (pinfunction "1_1") (pintype "passive"))
      (node (ref "J1-9P") (pin "14") (pinfunction "14_14") (pintype "passive"))
      (node (ref "R1-2P") (pin "2") (pinfunction "2_2") (pintype "passive"))
      (node (ref "U2-P") (pin "17") (pinfunction "VOUT_1_17") (pintype "bidirectional"))
      (node (ref "U2-P") (pin "18") (pinfunction "VOUT_2_18") (pintype "bidirectional"))
      (node (ref "U2-P") (pin "19") (pinfunction "VOUT_3_19") (pintype "bidirectional"))
      (node (ref "U2-P") (pin "20") (pinfunction "VOUT_4_20") (pintype "bidirectional"))
      (node (ref "U2-S") (pin "8") (pinfunction "VDD_8") (pintype "bidirectional"))
      (node (ref "U9-P") (pin "1") (pinfunction "VIN_1") (pintype "bidirectional"))
      (node (ref "U9-P") (pin "3") (pinfunction "EN_3") (pintype "bidirectional"))
    )
    (net (code "21") (name "ACCEL_ANALOG") (class "Default")
      (node (ref "C1-2S") (pin "1") (pinfunction "1_1") (pintype "passive"))
      (node (ref "R3-2S") (pin "2") (pinfunction "2_2") (pintype "passive"))
      (node (ref "U0-C") (pin "46") (pinfunction "PB0_46") (pintype "bidirectional"))
    )
    (net (code "22") (name "ADC-ERROR") (class "Default")
      (node (ref "D6-C") (pin "A") (pinfunction "A_A") (pintype "passive"))
      (node (ref "U0-C") (pin "59") (pinfunction "PE8_59") (pintype "bidirectional"))
    )
    (net (code "23") (name "ADC_ALERT") (class "Default")
      (node (ref "R4-2C") (pin "2") (pinfunction "2_2") (pintype "passive"))
      (node (ref "U0-C") (pin "98") (pinfunction "PC8_98") (pintype "bidirectional"))
      (node (ref "U2-C") (pin "2") (pinfunction "ALERT/RDY_2") (pintype "bidirectional"))
    )
    (net (code "24") (name "ARMED-LED") (class "Default")
      (node (ref "D0A-C") (pin "A") (pinfunction "A_A") (pintype "passive"))
      (node (ref "D0B-C") (pin "A") (pinfunction "A_A") (pintype "passive"))
      (node (ref "D0C-C") (pin "A") (pinfunction "A_A") (pintype "passive"))
      (node (ref "U0-C") (pin "53") (pinfunction "PF13_53") (pintype "bidirectional"))
    )
    (net (code "25") (name "BATT_MEAS") (class "Default")
      (node (ref "R3-11P") (pin "1") (pinfunction "1_1") (pintype "passive"))
      (node (ref "R4-11P") (pin "2") (pinfunction "2_2") (pintype "passive"))
    )
    (net (code "26") (name "BATT_MEASURE") (class "Default")
      (node (ref "U0-C") (pin "47") (pinfunction "PB1_47") (pintype "bidirectional"))
    )
    (net (code "27") (name "CENTRAL-ERROR") (class "Default")
      (node (ref "D2A-C") (pin "A") (pinfunction "A_A") (pintype "passive"))
      (node (ref "D2B-C") (pin "A") (pinfunction "A_A") (pintype "passive"))
      (node (ref "U0-C") (pin "55") (pinfunction "PF15_55") (pintype "bidirectional"))
    )
    (net (code "28") (name "CENTRAL-NOMINAL") (class "Default")
      (node (ref "D1A-C") (pin "A") (pinfunction "A_A") (pintype "passive"))
      (node (ref "D1B-C") (pin "A") (pinfunction "A_A") (pintype "passive"))
      (node (ref "U0-C") (pin "54") (pinfunction "PF14_54") (pintype "bidirectional"))
    )
    (net (code "29") (name "CLK-1") (class "Default")
      (node (ref "U0-C") (pin "41") (pinfunction "PA5_41") (pintype "bidirectional"))
      (node (ref "U13-S") (pin "2") (pinfunction "A_2") (pintype "bidirectional"))
      (node (ref "U3-S") (pin "P$8") (pinfunction "SCLK_P$8") (pintype "bidirectional"))
    )
    (net (code "30") (name "CLK-3") (class "Default")
      (node (ref "U0-C") (pin "111") (pinfunction "PC10_111") (pintype "bidirectional"))
      (node (ref "U1-C") (pin "6") (pinfunction "SCK_6") (pintype "bidirectional"))
    )
    (net (code "31") (name "CLK_1V8") (class "Default")
      (node (ref "U1-S") (pin "23") (pinfunction "SCL/SCLK_23") (pintype "bidirectional"))
      (node (ref "U13-S") (pin "4") (pinfunction "Y_4") (pintype "bidirectional"))
    )
    (net (code "32") (name "CMP_LDO_IN") (class "Default")
      (node (ref "R1-11P") (pin "1") (pinfunction "1_1") (pintype "passive"))
      (node (ref "R2-11P") (pin "2") (pinfunction "2_2") (pintype "passive"))
      (node (ref "U7-P") (pin "3") (pinfunction "1IN+_3") (pintype "bidirectional"))
      (node (ref "U7-P") (pin "5") (pinfunction "2IN+_5") (pintype "bidirectional"))
      (node (ref "U8-P") (pin "3") (pinfunction "1IN+_3") (pintype "bidirectional"))
      (node (ref "U8-P") (pin "5") (pinfunction "2IN+_5") (pintype "bidirectional"))
    )
    (net (code "33") (name "CMP_LDO_OUT_1") (class "Default")
      (node (ref "Q1-5P") (pin "2") (pinfunction "G1_2") (pintype "bidirectional"))
      (node (ref "R2-5P") (pin "2") (pinfunction "2_2") (pintype "passive"))
      (node (ref "U7-P") (pin "1") (pinfunction "1OUT_1") (pintype "bidirectional"))
    )
    (net (code "34") (name "CMP_LDO_OUT_2") (class "Default")
      (node (ref "Q1-5P") (pin "4") (pinfunction "G2_4") (pintype "bidirectional"))
      (node (ref "R6-5P") (pin "2") (pinfunction "2_2") (pintype "passive"))
      (node (ref "U7-P") (pin "7") (pinfunction "2OUT_7") (pintype "bidirectional"))
    )
    (net (code "35") (name "CMP_LDO_OUT_3") (class "Default")
      (node (ref "Q1-6P") (pin "2") (pinfunction "G1_2") (pintype "bidirectional"))
      (node (ref "R2-6P") (pin "2") (pinfunction "2_2") (pintype "passive"))
      (node (ref "U8-P") (pin "1") (pinfunction "1OUT_1") (pintype "bidirectional"))
    )
    (net (code "36") (name "CMP_LDO_OUT_4") (class "Default")
      (node (ref "Q1-6P") (pin "4") (pinfunction "G2_4") (pintype "bidirectional"))
      (node (ref "R6-6P") (pin "2") (pinfunction "2_2") (pintype "passive"))
      (node (ref "U8-P") (pin "7") (pinfunction "2OUT_7") (pintype "bidirectional"))
    )
    (net (code "37") (name "CMP_RAIL") (class "Default")
      (node (ref "R3-9P") (pin "1") (pinfunction "1_1") (pintype "passive"))
      (node (ref "R4-9P") (pin "2") (pinfunction "2_2") (pintype "passive"))
      (node (ref "U7-P") (pin "2") (pinfunction "1IN-_2") (pintype "bidirectional"))
      (node (ref "U7-P") (pin "6") (pinfunction "2IN-_6") (pintype "bidirectional"))
      (node (ref "U8-P") (pin "2") (pinfunction "1IN-_2") (pintype "bidirectional"))
      (node (ref "U8-P") (pin "6") (pinfunction "2IN-_6") (pintype "bidirectional"))
    )
    (net (code "38") (name "CS-3") (class "Default")
      (node (ref "U0-C") (pin "114") (pinfunction "PD0_114") (pintype "bidirectional"))
      (node (ref "U1-C") (pin "1") (pinfunction "~{CS}_1") (pintype "bidirectional"))
    )
    (net (code "39") (name "CS1") (class "Default")
      (node (ref "U0-C") (pin "44") (pinfunction "PC4_44") (pintype "bidirectional"))
      (node (ref "U14-S") (pin "2") (pinfunction "A_2") (pintype "bidirectional"))
    )
    (net (code "40") (name "CS1_1V8") (class "Default")
      (node (ref "U1-S") (pin "22") (pinfunction "NCS_22") (pintype "bidirectional"))
      (node (ref "U14-S") (pin "4") (pinfunction "Y_4") (pintype "bidirectional"))
    )
    (net (code "41") (name "CS2") (class "Default")
      (node (ref "U0-C") (pin "45") (pinfunction "PC5_45") (pintype "bidirectional"))
      (node (ref "U3-S") (pin "P$4") (pinfunction "CSB_P$4") (pintype "bidirectional"))
      (node (ref "U3-S") (pin "P$5") (pinfunction "CSB_P$5") (pintype "bidirectional"))
    )
    (net (code "43") (name "CTS") (class "Default")
      (node (ref "J1-9P") (pin "13") (pinfunction "13_13") (pintype "passive"))
      (node (ref "U0-C") (pin "34") (pinfunction "PA0_34") (pintype "bidirectional"))
    )
    (net (code "44") (name "D+") (class "Default")
      (node (ref "R2-J2C") (pin "2") (pinfunction "2_2") (pintype "passive"))
      (node (ref "R3-J2C") (pin "1") (pinfunction "1_1") (pintype "passive"))
      (node (ref "U0-C") (pin "104") (pinfunction "PA12_104") (pintype "bidirectional"))
    )
    (net (code "45") (name "D-") (class "Default")
      (node (ref "R1-J2C") (pin "2") (pinfunction "2_2") (pintype "passive"))
      (node (ref "U0-C") (pin "103") (pinfunction "PA11_103") (pintype "bidirectional"))
    )
    (net (code "46") (name "DISARM_INPUT") (class "Default")
      (node (ref "R0-0C") (pin "2") (pinfunction "2_2") (pintype "passive"))
      (node (ref "S0-0C") (pin "3") (pinfunction "P_3") (pintype "passive"))
      (node (ref "U0-C") (pin "89") (pinfunction "PG4_89") (pintype "bidirectional"))
    )
    (net (code "47") (name "DROGUE-LED") (class "Default")
      (node (ref "D3-C") (pin "A") (pinfunction "A_A") (pintype "passive"))
      (node (ref "U0-C") (pin "56") (pinfunction "PG0_56") (pintype "bidirectional"))
    )
    (net (code "48") (name "FET_A") (class "Default")
      (node (ref "J2-CHARGETERMINAL") (pin "2") (pinfunction "2_2") (pintype "bidirectional"))
      (node (ref "Q1-5P") (pin "7") (pinfunction "D1_1_7") (pintype "bidirectional"))
      (node (ref "Q1-5P") (pin "8") (pinfunction "D1_2_8") (pintype "bidirectional"))
      (node (ref "R3-5P") (pin "1") (pinfunction "1_1") (pintype "passive"))
    )
    (net (code "49") (name "FET_B") (class "Default")
      (node (ref "J2-CHARGETERMINAL") (pin "4") (pinfunction "4_4") (pintype "bidirectional"))
      (node (ref "Q1-5P") (pin "5") (pinfunction "D2_1_5") (pintype "bidirectional"))
      (node (ref "Q1-5P") (pin "6") (pinfunction "D2_2_6") (pintype "bidirectional"))
      (node (ref "R7-5P") (pin "1") (pinfunction "1_1") (pintype "passive"))
    )
    (net (code "50") (name "FET_C") (class "Default")
      (node (ref "J2-CHARGETERMINAL") (pin "6") (pinfunction "6_6") (pintype "bidirectional"))
      (node (ref "Q1-6P") (pin "7") (pinfunction "D1_1_7") (pintype "bidirectional"))
      (node (ref "Q1-6P") (pin "8") (pinfunction "D1_2_8") (pintype "bidirectional"))
      (node (ref "R3-6P") (pin "1") (pinfunction "1_1") (pintype "passive"))
    )
    (net (code "51") (name "FET_D") (class "Default")
      (node (ref "J2-CHARGETERMINAL") (pin "8") (pinfunction "8_8") (pintype "bidirectional"))
      (node (ref "Q1-6P") (pin "5") (pinfunction "D2_1_5") (pintype "bidirectional"))
      (node (ref "Q1-6P") (pin "6") (pinfunction "D2_2_6") (pintype "bidirectional"))
      (node (ref "R7-6P") (pin "1") (pinfunction "1_1") (pintype "passive"))
    )
    (net (code "52") (name "FIRE_A") (class "Default")
      (node (ref "R1-5P") (pin "2") (pinfunction "2_2") (pintype "passive"))
      (node (ref "R2-5P") (pin "1") (pinfunction "1_1") (pintype "passive"))
      (node (ref "U0-C") (pin "11") (pinfunction "PF1_11") (pintype "bidirectional"))
    )
    (net (code "53") (name "FIRE_B") (class "Default")
      (node (ref "R5-5P") (pin "2") (pinfunction "2_2") (pintype "passive"))
      (node (ref "R6-5P") (pin "1") (pinfunction "1_1") (pintype "passive"))
      (node (ref "U0-C") (pin "12") (pinfunction "PF2_12") (pintype "bidirectional"))
    )
    (net (code "54") (name "FIRE_C") (class "Default")
      (node (ref "R1-6P") (pin "2") (pinfunction "2_2") (pintype "passive"))
      (node (ref "R2-6P") (pin "1") (pinfunction "1_1") (pintype "passive"))
      (node (ref "U0-C") (pin "13") (pinfunction "PF3_13") (pintype "bidirectional"))
    )
    (net (code "55") (name "FIRE_D") (class "Default")
      (node (ref "R5-6P") (pin "2") (pinfunction "2_2") (pintype "passive"))
      (node (ref "R6-6P") (pin "1") (pinfunction "1_1") (pintype "passive"))
      (node (ref "U0-C") (pin "14") (pinfunction "PF4_14") (pintype "bidirectional"))
    )
    (net (code "56") (name "GND") (class "Default")
      (node (ref "1S_LIPO") (pin "2") (pinfunction "2_2") (pintype "bidirectional"))
      (node (ref "AT1-S") (pin "2") (pinfunction "GND_1_2") (pintype "bidirectional"))
      (node (ref "AT1-S") (pin "3") (pinfunction "GND_2_3") (pintype "bidirectional"))
      (node (ref "AT1-S") (pin "4") (pinfunction "GND_3_4") (pintype "bidirectional"))
      (node (ref "C1") (pin "2") (pinfunction "2_2") (pintype "passive"))
      (node (ref "C1-0C") (pin "2") (pinfunction "2_2") (pintype "passive"))
      (node (ref "C1-0S") (pin "2") (pinfunction "2_2") (pintype "passive"))
      (node (ref "C1-11P") (pin "2") (pinfunction "2_2") (pintype "passive"))
      (node (ref "C1-1P") (pin "2") (pinfunction "2_2") (pintype "passive"))
      (node (ref "C1-1S") (pin "2") (pinfunction "2_2") (pintype "passive"))
      (node (ref "C1-2C") (pin "2") (pinfunction "2_2") (pintype "passive"))
      (node (ref "C1-2P") (pin "2") (pinfunction "2_2") (pintype "passive"))
      (node (ref "C1-2S") (pin "2") (pinfunction "2_2") (pintype "passive"))
      (node (ref "C1-3S") (pin "2") (pinfunction "2_2") (pintype "passive"))
      (node (ref "C1-C") (pin "2") (pinfunction "2_2") (pintype "passive"))
      (node (ref "C10-0C") (pin "2") (pinfunction "2_2") (pintype "passive"))
      (node (ref "C11-0C") (pin "2") (pinfunction "2_2") (pintype "passive"))
      (node (ref "C12-0C") (pin "2") (pinfunction "2_2") (pintype "passive"))
      (node (ref "C13-0C") (pin "2") (pinfunction "2_2") (pintype "passive"))
      (node (ref "C14-0C") (pin "2") (pinfunction "2_2") (pintype "passive"))
      (node (ref "C15-0C") (pin "2") (pinfunction "2_2") (pintype "passive"))
      (node (ref "C16-0C") (pin "2") (pinfunction "2_2") (pintype "passive"))
      (node (ref "C17-0C") (pin "2") (pinfunction "2_2") (pintype "passive"))
      (node (ref "C2") (pin "2") (pinfunction "2_2") (pintype "passive"))
      (node (ref "C2-0C") (pin "2") (pinfunction "2_2") (pintype "passive"))
      (node (ref "C2-0S") (pin "2") (pinfunction "2_2") (pintype "passive"))
      (node (ref "C2-1P") (pin "2") (pinfunction "2_2") (pintype "passive"))
      (node (ref "C2-1S") (pin "2") (pinfunction "2_2") (pintype "passive"))
      (node (ref "C2-2P") (pin "2") (pinfunction "2_2") (pintype "passive"))
      (node (ref "C2-2S") (pin "2") (pinfunction "2_2") (pintype "passive"))
      (node (ref "C2-9P") (pin "2") (pinfunction "2_2") (pintype "passive"))
      (node (ref "C3-0C") (pin "2") (pinfunction "2_2") (pintype "passive"))
      (node (ref "C3-1S") (pin "2") (pinfunction "2_2") (pintype "passive"))
      (node (ref "C3-9P") (pin "2") (pinfunction "2_2") (pintype "passive"))
      (node (ref "C4-0C") (pin "2") (pinfunction "2_2") (pintype "passive"))
      (node (ref "C4-2P") (pin "2") (pinfunction "2_2") (pintype "passive"))
      (node (ref "C4-9P") (pin "2") (pinfunction "2_2") (pintype "passive"))
      (node (ref "C5-0C") (pin "2") (pinfunction "2_2") (pintype "passive"))
      (node (ref "C5-2P") (pin "2") (pinfunction "2_2") (pintype "passive"))
      (node (ref "C6-0C") (pin "2") (pinfunction "2_2") (pintype "passive"))
      (node (ref "C7-0C") (pin "2") (pinfunction "2_2") (pintype "passive"))
      (node (ref "C8-0C") (pin "2") (pinfunction "2_2") (pintype "passive"))
      (node (ref "C9-0C") (pin "2") (pinfunction "2_2") (pintype "passive"))
      (node (ref "J1-9P") (pin "15") (pinfunction "15_15") (pintype "passive"))
      (node (ref "J2-C") (pin "5") (pinfunction "GND_5") (pintype "power_in"))
      (node (ref "J2-C") (pin "S1") (pinfunction "SHIELD_S1") (pintype "power_in"))
      (node (ref "J2-C") (pin "S2") (pinfunction "SHIELD_S2") (pintype "power_in"))
      (node (ref "J2-C") (pin "S3") (pinfunction "SHIELD_S3") (pintype "power_in"))
      (node (ref "J2-C") (pin "S4") (pinfunction "SHIELD_S4") (pintype "power_in"))
      (node (ref "JP1") (pin "1") (pinfunction "1_1") (pintype "passive"))
      (node (ref "Q1-5P") (pin "1") (pinfunction "S1_1") (pintype "bidirectional"))
      (node (ref "Q1-5P") (pin "3") (pinfunction "S2_3") (pintype "bidirectional"))
      (node (ref "Q1-6P") (pin "1") (pinfunction "S1_1") (pintype "bidirectional"))
      (node (ref "Q1-6P") (pin "3") (pinfunction "S2_3") (pintype "bidirectional"))
      (node (ref "R0-0C") (pin "1") (pinfunction "1_1") (pintype "passive"))
      (node (ref "R0A-C") (pin "2") (pinfunction "2_2") (pintype "passive"))
      (node (ref "R0B-C") (pin "2") (pinfunction "2_2") (pintype "passive"))
      (node (ref "R0C-C") (pin "2") (pinfunction "2_2") (pintype "passive"))
      (node (ref "R1-0C") (pin "2") (pinfunction "2_2") (pintype "passive"))
      (node (ref "R1-1S") (pin "2") (pinfunction "2_2") (pintype "passive"))
      (node (ref "R1-2S") (pin "2") (pinfunction "2_2") (pintype "passive"))
      (node (ref "R1-3S") (pin "2") (pinfunction "2_2") (pintype "passive"))
      (node (ref "R1-4S") (pin "2") (pinfunction "2_2") (pintype "passive"))
      (node (ref "R1-5P") (pin "1") (pinfunction "1_1") (pintype "passive"))
      (node (ref "R1-6P") (pin "1") (pinfunction "1_1") (pintype "passive"))
      (node (ref "R1A-C") (pin "2") (pinfunction "2_2") (pintype "passive"))
      (node (ref "R1A-S") (pin "2") (pinfunction "2_2") (pintype "passive"))
      (node (ref "R1B-C") (pin "2") (pinfunction "2_2") (pintype "passive"))
      (node (ref "R1B-S") (pin "2") (pinfunction "2_2") (pintype "passive"))
      (node (ref "R2-11P") (pin "1") (pinfunction "1_1") (pintype "passive"))
      (node (ref "R2-1P") (pin "1") (pinfunction "1_1") (pintype "passive"))
      (node (ref "R2-1S") (pin "2") (pinfunction "2_2") (pintype "passive"))
      (node (ref "R2-2P") (pin "1") (pinfunction "1_1") (pintype "passive"))
      (node (ref "R2-2S") (pin "2") (pinfunction "2_2") (pintype "passive"))
      (node (ref "R2-3S") (pin "2") (pinfunction "2_2") (pintype "passive"))
      (node (ref "R2-4S") (pin "2") (pinfunction "2_2") (pintype "passive"))
      (node (ref "R2-9P") (pin "1") (pinfunction "1_1") (pintype "passive"))
      (node (ref "R2A-C") (pin "2") (pinfunction "2_2") (pintype "passive"))
      (node (ref "R2A-S") (pin "2") (pinfunction "2_2") (pintype "passive"))
      (node (ref "R2B-C") (pin "2") (pinfunction "2_2") (pintype "passive"))
      (node (ref "R2B-S") (pin "2") (pinfunction "2_2") (pintype "passive"))
      (node (ref "R3-11P") (pin "2") (pinfunction "2_2") (pintype "passive"))
      (node (ref "R3-2C") (pin "1") (pinfunction "1_1") (pintype "passive"))
      (node (ref "R3-4S") (pin "2") (pinfunction "2_2") (pintype "passive"))
      (node (ref "R3-C") (pin "2") (pinfunction "2_2") (pintype "passive"))
      (node (ref "R4-5P") (pin "1") (pinfunction "1_1") (pintype "passive"))
      (node (ref "R4-6P") (pin "1") (pinfunction "1_1") (pintype "passive"))
      (node (ref "R4-9P") (pin "1") (pinfunction "1_1") (pintype "passive"))
      (node (ref "R4-C") (pin "2") (pinfunction "2_2") (pintype "passive"))
      (node (ref "R5-5P") (pin "1") (pinfunction "1_1") (pintype "passive"))
      (node (ref "R5-6P") (pin "1") (pinfunction "1_1") (pintype "passive"))
      (node (ref "R5-C") (pin "2") (pinfunction "2_2") (pintype "passive"))
      (node (ref "R6-C") (pin "2") (pinfunction "2_2") (pintype "passive"))
      (node (ref "R8-5P") (pin "1") (pinfunction "1_1") (pintype "passive"))
      (node (ref "R8-6P") (pin "1") (pinfunction "1_1") (pintype "passive"))
      (node (ref "S1-0C") (pin "3") (pinfunction "P_3") (pintype "passive"))
      (node (ref "S1-0C") (pin "4") (pinfunction "P1_4") (pintype "passive"))
      (node (ref "U0-C") (pin "107") (pinfunction "VSS_7_107") (pintype "power_in"))
      (node (ref "U0-C") (pin "120") (pinfunction "VSS_8_120") (pintype "power_in"))
      (node (ref "U0-C") (pin "130") (pinfunction "VSS_9_130") (pintype "power_in"))
      (node (ref "U0-C") (pin "16") (pinfunction "VSS_1_16") (pintype "power_in"))
      (node (ref "U0-C") (pin "31") (pinfunction "VSSA_31") (pintype "power_in"))
      (node (ref "U0-C") (pin "38") (pinfunction "VSS_2_38") (pintype "power_in"))
      (node (ref "U0-C") (pin "51") (pinfunction "VSS_3_51") (pintype "power_in"))
      (node (ref "U0-C") (pin "61") (pinfunction "VSS_4_61") (pintype "power_in"))
      (node (ref "U0-C") (pin "83") (pinfunction "VSS_5_83") (pintype "power_in"))
      (node (ref "U0-C") (pin "94") (pinfunction "VSS_6_94") (pintype "power_in"))
      (node (ref "U0-S") (pin "2") (pinfunction "GND_2") (pintype "bidirectional"))
      (node (ref "U1-C") (pin "8") (pinfunction "VSS_8") (pintype "bidirectional"))
      (node (ref "U1-P") (pin "2") (pinfunction "VSS_2") (pintype "power_in"))
      (node (ref "U1-S") (pin "18") (pinfunction "GND_18") (pintype "bidirectional"))
      (node (ref "U1-S") (pin "20") (pinfunction "RESV.GND_20") (pintype "bidirectional"))
      (node (ref "U11-S") (pin "3") (pinfunction "GND_3") (pintype "bidirectional"))
      (node (ref "U12-S") (pin "3") (pinfunction "GND_3") (pintype "bidirectional"))
      (node (ref "U13-S") (pin "3") (pinfunction "GND_3") (pintype "bidirectional"))
      (node (ref "U14-S") (pin "3") (pinfunction "GND_3") (pintype "bidirectional"))
      (node (ref "U2-C") (pin "3") (pinfunction "GND_3") (pintype "bidirectional"))
      (node (ref "U2-P") (pin "12") (pinfunction "MODE_12") (pintype "bidirectional"))
      (node (ref "U2-P") (pin "13") (pinfunction "SGND_1_13") (pintype "bidirectional"))
      (node (ref "U2-P") (pin "3") (pinfunction "PGND_3") (pintype "bidirectional"))
      (node (ref "U2-S") (pin "7") (pinfunction "VSS_7") (pintype "bidirectional"))
      (node (ref "U3-S") (pin "P$2") (pinfunction "PS_P$2") (pintype "bidirectional"))
      (node (ref "U3-S") (pin "P$3") (pinfunction "GND_P$3") (pintype "bidirectional"))
      (node (ref "U4-S") (pin "12") (pinfunction "GND_12") (pintype "bidirectional"))
      (node (ref "U4-S") (pin "19") (pinfunction "GND_19") (pintype "bidirectional"))
      (node (ref "U4-S") (pin "3") (pinfunction "GND_3") (pintype "bidirectional"))
      (node (ref "U4-S") (pin "8") (pinfunction "GND_8") (pintype "bidirectional"))
      (node (ref "U7-P") (pin "4") (pinfunction "GND_4") (pintype "bidirectional"))
      (node (ref "U8-P") (pin "4") (pinfunction "GND_4") (pintype "bidirectional"))
      (node (ref "U9-P") (pin "2") (pinfunction "GND_2") (pintype "bidirectional"))
    )
    (net (code "57") (name "HOLD") (class "Default")
      (node (ref "U0-C") (pin "77") (pinfunction "PD8_77") (pintype "bidirectional"))
      (node (ref "U1-C") (pin "5") (pinfunction "~{HOLD}/IO3_5") (pintype "bidirectional"))
    )
    (net (code "58") (name "ID") (class "Default")
      (node (ref "J2-C") (pin "4") (pinfunction "ID_4") (pintype "bidirectional"))
      (node (ref "U0-C") (pin "102") (pinfunction "PA10_102") (pintype "bidirectional"))
    )
    (net (code "59") (name "MAIN-LED") (class "Default")
      (node (ref "D4-C") (pin "A") (pinfunction "A_A") (pintype "passive"))
      (node (ref "U0-C") (pin "57") (pinfunction "PG1_57") (pintype "bidirectional"))
    )
    (net (code "60") (name "MASTER_RX-1") (class "Default")
      (node (ref "U0-C") (pin "96") (pinfunction "PC6_96") (pintype "bidirectional"))
      (node (ref "U4-S") (pin "9") (pinfunction "TX_9") (pintype "bidirectional"))
    )
    (net (code "61") (name "MASTER_RX-2") (class "Default")
      (node (ref "J1-9P") (pin "7") (pinfunction "7_7") (pintype "passive"))
      (node (ref "U0-C") (pin "37") (pinfunction "PA3_37") (pintype "bidirectional"))
    )
    (net (code "62") (name "MASTER_TX-1") (class "Default")
      (node (ref "U0-C") (pin "95") (pinfunction "VDD_8_95") (pintype "power_in"))
      (node (ref "U4-S") (pin "10") (pinfunction "RX_10") (pintype "bidirectional"))
    )
    (net (code "63") (name "MASTER_TX-2") (class "Default")
      (node (ref "J1-9P") (pin "9") (pinfunction "9_9") (pintype "passive"))
      (node (ref "U0-C") (pin "36") (pinfunction "PA2_36") (pintype "bidirectional"))
    )
    (net (code "64") (name "MISO-1") (class "Default")
      (node (ref "U0-C") (pin "42") (pinfunction "PA6_42") (pintype "bidirectional"))
      (node (ref "U11-S") (pin "4") (pinfunction "Y_4") (pintype "bidirectional"))
    )
    (net (code "65") (name "MISO-3") (class "Default")
      (node (ref "U0-C") (pin "112") (pinfunction "PC11_112") (pintype "bidirectional"))
      (node (ref "U1-C") (pin "2") (pinfunction "SO/IO1_2") (pintype "bidirectional"))
    )
    (net (code "66") (name "MISO_1V8") (class "Default")
      (node (ref "U1-S") (pin "9") (pinfunction "SDO/AD0_9") (pintype "bidirectional"))
      (node (ref "U11-S") (pin "2") (pinfunction "A_2") (pintype "bidirectional"))
    )
    (net (code "67") (name "MOSI-1") (class "Default")
      (node (ref "U0-C") (pin "43") (pinfunction "PA7_43") (pintype "bidirectional"))
      (node (ref "U12-S") (pin "2") (pinfunction "A_2") (pintype "bidirectional"))
      (node (ref "U3-S") (pin "P$6") (pinfunction "SDO_P$6") (pintype "bidirectional"))
      (node (ref "U3-S") (pin "P$7") (pinfunction "SDI_P$7") (pintype "bidirectional"))
    )
    (net (code "68") (name "MOSI-3") (class "Default")
      (node (ref "U0-C") (pin "113") (pinfunction "PC12_113") (pintype "bidirectional"))
      (node (ref "U1-C") (pin "4") (pinfunction "SI/IO0_4") (pintype "bidirectional"))
    )
    (net (code "69") (name "MOSI_1V8") (class "Default")
      (node (ref "U1-S") (pin "24") (pinfunction "SDA/SDI_24") (pintype "bidirectional"))
      (node (ref "U12-S") (pin "4") (pinfunction "Y_4") (pintype "bidirectional"))
    )
    (net (code "70") (name "N$5") (class "Default")
      (node (ref "U0-C") (pin "97") (pinfunction "PC7_97") (pintype "bidirectional"))
    )
    (net (code "72") (name "NRST") (class "Default")
      (node (ref "C15-0C") (pin "1") (pinfunction "1_1") (pintype "passive"))
      (node (ref "R2-J1C") (pin "2") (pinfunction "2_2") (pintype "passive"))
      (node (ref "S1-0C") (pin "1") (pinfunction "S_1") (pintype "passive"))
      (node (ref "S1-0C") (pin "2") (pinfunction "S1_2") (pintype "passive"))
      (node (ref "U0-C") (pin "25") (pinfunction "NRST_25") (pintype "input"))
    )
    (net (code "73") (name "Net-(D0A-C-PadC)") (class "Default")
      (node (ref "D0A-C") (pin "C") (pinfunction "C_C") (pintype "passive"))
      (node (ref "R0A-C") (pin "1") (pinfunction "1_1") (pintype "passive"))
    )
    (net (code "74") (name "Net-(D0B-C-PadC)") (class "Default")
      (node (ref "D0B-C") (pin "C") (pinfunction "C_C") (pintype "passive"))
      (node (ref "R0B-C") (pin "1") (pinfunction "1_1") (pintype "passive"))
    )
    (net (code "75") (name "Net-(D0C-C-PadC)") (class "Default")
      (node (ref "D0C-C") (pin "C") (pinfunction "C_C") (pintype "passive"))
      (node (ref "R0C-C") (pin "1") (pinfunction "1_1") (pintype "passive"))
    )
    (net (code "76") (name "Net-(D1-1P-PadC)") (class "Default")
      (node (ref "D1-1P") (pin "C") (pinfunction "C_C") (pintype "passive"))
      (node (ref "R1-1P") (pin "1") (pinfunction "1_1") (pintype "passive"))
    )
    (net (code "77") (name "Net-(D1-1S-PadC)") (class "Default")
      (node (ref "D1-1S") (pin "C") (pinfunction "C_C") (pintype "passive"))
      (node (ref "R1-1S") (pin "1") (pinfunction "1_1") (pintype "passive"))
    )
    (net (code "78") (name "Net-(D1-2S-PadC)") (class "Default")
      (node (ref "D1-2S") (pin "C") (pinfunction "C_C") (pintype "passive"))
      (node (ref "R1-2S") (pin "1") (pinfunction "1_1") (pintype "passive"))
    )
    (net (code "79") (name "Net-(D1-3S-PadC)") (class "Default")
      (node (ref "D1-3S") (pin "C") (pinfunction "C_C") (pintype "passive"))
      (node (ref "R1-3S") (pin "1") (pinfunction "1_1") (pintype "passive"))
    )
    (net (code "80") (name "Net-(D1-4S-PadC)") (class "Default")
      (node (ref "D1-4S") (pin "C") (pinfunction "C_C") (pintype "passive"))
      (node (ref "R1-4S") (pin "1") (pinfunction "1_1") (pintype "passive"))
    )
    (net (code "81") (name "Net-(D1A-C-PadC)") (class "Default")
      (node (ref "D1A-C") (pin "C") (pinfunction "C_C") (pintype "passive"))
      (node (ref "R1A-C") (pin "1") (pinfunction "1_1") (pintype "passive"))
    )
    (net (code "82") (name "Net-(D1A-S-PadC)") (class "Default")
      (node (ref "D1A-S") (pin "C") (pinfunction "C_C") (pintype "passive"))
      (node (ref "R1A-S") (pin "1") (pinfunction "1_1") (pintype "passive"))
    )
    (net (code "83") (name "Net-(D1B-C-PadC)") (class "Default")
      (node (ref "D1B-C") (pin "C") (pinfunction "C_C") (pintype "passive"))
      (node (ref "R1B-C") (pin "1") (pinfunction "1_1") (pintype "passive"))
    )
    (net (code "84") (name "Net-(D1B-S-PadC)") (class "Default")
      (node (ref "D1B-S") (pin "C") (pinfunction "C_C") (pintype "passive"))
      (node (ref "R1B-S") (pin "1") (pinfunction "1_1") (pintype "passive"))
    )
    (net (code "85") (name "Net-(D2-1S-PadC)") (class "Default")
      (node (ref "D2-1S") (pin "C") (pinfunction "C_C") (pintype "passive"))
      (node (ref "R2-1S") (pin "1") (pinfunction "1_1") (pintype "passive"))
    )
    (net (code "86") (name "Net-(D2-2S-PadC)") (class "Default")
      (node (ref "D2-2S") (pin "C") (pinfunction "C_C") (pintype "passive"))
      (node (ref "R2-2S") (pin "1") (pinfunction "1_1") (pintype "passive"))
    )
    (net (code "87") (name "Net-(D2-3S-PadC)") (class "Default")
      (node (ref "D2-3S") (pin "C") (pinfunction "C_C") (pintype "passive"))
      (node (ref "R2-3S") (pin "1") (pinfunction "1_1") (pintype "passive"))
    )
    (net (code "88") (name "Net-(D2-4S-PadC)") (class "Default")
      (node (ref "D2-4S") (pin "C") (pinfunction "C_C") (pintype "passive"))
      (node (ref "R2-4S") (pin "1") (pinfunction "1_1") (pintype "passive"))
    )
    (net (code "89") (name "Net-(D2A-C-PadC)") (class "Default")
      (node (ref "D2A-C") (pin "C") (pinfunction "C_C") (pintype "passive"))
      (node (ref "R2A-C") (pin "1") (pinfunction "1_1") (pintype "passive"))
    )
    (net (code "90") (name "Net-(D2A-S-PadC)") (class "Default")
      (node (ref "D2A-S") (pin "C") (pinfunction "C_C") (pintype "passive"))
      (node (ref "R2A-S") (pin "1") (pinfunction "1_1") (pintype "passive"))
    )
    (net (code "91") (name "Net-(D2B-C-PadC)") (class "Default")
      (node (ref "D2B-C") (pin "C") (pinfunction "C_C") (pintype "passive"))
      (node (ref "R2B-C") (pin "1") (pinfunction "1_1") (pintype "passive"))
    )
    (net (code "92") (name "Net-(D2B-S-PadC)") (class "Default")
      (node (ref "D2B-S") (pin "C") (pinfunction "C_C") (pintype "passive"))
      (node (ref "R2B-S") (pin "1") (pinfunction "1_1") (pintype "passive"))
    )
    (net (code "93") (name "Net-(D3-4S-PadC)") (class "Default")
      (node (ref "D3-4S") (pin "C") (pinfunction "C_C") (pintype "passive"))
      (node (ref "R3-4S") (pin "1") (pinfunction "1_1") (pintype "passive"))
    )
    (net (code "94") (name "Net-(D3-C-PadC)") (class "Default")
      (node (ref "D3-C") (pin "C") (pinfunction "C_C") (pintype "passive"))
      (node (ref "R3-C") (pin "1") (pinfunction "1_1") (pintype "passive"))
    )
    (net (code "95") (name "Net-(D4-C-PadC)") (class "Default")
      (node (ref "D4-C") (pin "C") (pinfunction "C_C") (pintype "passive"))
      (node (ref "R4-C") (pin "1") (pinfunction "1_1") (pintype "passive"))
    )
    (net (code "96") (name "Net-(D5-C-PadC)") (class "Default")
      (node (ref "D5-C") (pin "C") (pinfunction "C_C") (pintype "passive"))
      (node (ref "R5-C") (pin "1") (pinfunction "1_1") (pintype "passive"))
    )
    (net (code "97") (name "Net-(D6-C-PadC)") (class "Default")
      (node (ref "D6-C") (pin "C") (pinfunction "C_C") (pintype "passive"))
      (node (ref "R6-C") (pin "1") (pinfunction "1_1") (pintype "passive"))
    )
    (net (code "98") (name "Net-(J2-C-D+)") (class "Default")
      (node (ref "J2-C") (pin "3") (pinfunction "D+_3") (pintype "bidirectional"))
      (node (ref "R2-J2C") (pin "1") (pinfunction "1_1") (pintype "passive"))
    )
    (net (code "99") (name "Net-(J2-C-D-)") (class "Default")
      (node (ref "J2-C") (pin "2") (pinfunction "D-_2") (pintype "bidirectional"))
      (node (ref "R1-J2C") (pin "1") (pinfunction "1_1") (pintype "passive"))
    )
    (net (code "100") (name "Net-(JP1-Pad5)") (class "Default")
      (node (ref "JP1") (pin "5") (pinfunction "5_5") (pintype "passive"))
      (node (ref "R1-J1C") (pin "1") (pinfunction "1_1") (pintype "passive"))
    )
    (net (code "101") (name "Net-(JP1-Pad6)") (class "Default")
      (node (ref "JP1") (pin "6") (pinfunction "6_6") (pintype "passive"))
      (node (ref "R2-J1C") (pin "1") (pinfunction "1_1") (pintype "passive"))
    )
    (net (code "102") (name "Net-(L1-0S-1)") (class "Default")
      (node (ref "L1-0S") (pin "P$1") (pinfunction "1_P$1") (pintype "passive"))
      (node (ref "U0-S") (pin "5") (pinfunction "SW_5") (pintype "bidirectional"))
    )
    (net (code "103") (name "Net-(Q1-B)") (class "Default")
      (node (ref "Q1") (pin "1") (pinfunction "B_1") (pintype "passive"))
      (node (ref "R2") (pin "2") (pinfunction "2_2") (pintype "passive"))
    )
    (net (code "104") (name "Net-(U0-C-BOOT0)") (class "Default")
      (node (ref "R1-0C") (pin "1") (pinfunction "1_1") (pintype "passive"))
      (node (ref "U0-C") (pin "138") (pinfunction "BOOT0_138") (pintype "bidirectional"))
    )
    (net (code "105") (name "Net-(U0-C-VCAP_1)") (class "Default")
      (node (ref "C16-0C") (pin "1") (pinfunction "1_1") (pintype "passive"))
      (node (ref "U0-C") (pin "71") (pinfunction "VCAP_1_71") (pintype "bidirectional"))
    )
    (net (code "106") (name "Net-(U0-C-VCAP_2)") (class "Default")
      (node (ref "C17-0C") (pin "1") (pinfunction "1_1") (pintype "passive"))
      (node (ref "U0-C") (pin "106") (pinfunction "VCAP_2_106") (pintype "bidirectional"))
    )
    (net (code "107") (name "Net-(U1-P-PROG)") (class "Default")
      (node (ref "R2-1P") (pin "2") (pinfunction "2_2") (pintype "passive"))
      (node (ref "U1-P") (pin "5") (pinfunction "PROG_5") (pintype "bidirectional"))
    )
    (net (code "108") (name "Net-(U1-P-STAT)") (class "Default")
      (node (ref "R1-1P") (pin "2") (pinfunction "2_2") (pintype "passive"))
      (node (ref "U1-P") (pin "1") (pinfunction "STAT_1") (pintype "bidirectional"))
    )
    (net (code "109") (name "Net-(U1-S-REGOUT)") (class "Default")
      (node (ref "C1-1S") (pin "1") (pinfunction "1_1") (pintype "passive"))
      (node (ref "U1-S") (pin "10") (pinfunction "REGOUT_10") (pintype "bidirectional"))
    )
    (net (code "110") (name "Net-(U2-C-ADDR)") (class "Default")
      (node (ref "R3-2C") (pin "2") (pinfunction "2_2") (pintype "passive"))
      (node (ref "U2-C") (pin "1") (pinfunction "ADDR_1") (pintype "bidirectional"))
    )
    (net (code "111") (name "Net-(U2-P-LX1_1)") (class "Default")
      (node (ref "L1-2P") (pin "2") (pinfunction "2_2") (pintype "bidirectional"))
      (node (ref "U2-P") (pin "4") (pinfunction "LX1_1_4") (pintype "bidirectional"))
    )
    (net (code "112") (name "Net-(U2-P-LX2_1)") (class "Default")
      (node (ref "L1-2P") (pin "1") (pinfunction "1_1") (pintype "bidirectional"))
      (node (ref "U2-P") (pin "1") (pinfunction "LX2_1_1") (pintype "bidirectional"))
    )
    (net (code "113") (name "Net-(U2-S-VOUT)") (class "Default")
      (node (ref "R3-2S") (pin "1") (pinfunction "1_1") (pintype "passive"))
      (node (ref "U2-S") (pin "5") (pinfunction "VOUT_5") (pintype "bidirectional"))
    )
    (net (code "114") (name "OSC_IN") (class "Default")
      (node (ref "C1") (pin "1") (pinfunction "1_1") (pintype "passive"))
      (node (ref "U0-C") (pin "23") (pinfunction "PH0_23") (pintype "bidirectional"))
      (node (ref "Y1-C") (pin "3") (pinfunction "2_3") (pintype "passive"))
    )
    (net (code "115") (name "OSC_OUT") (class "Default")
      (node (ref "C2") (pin "1") (pinfunction "1_1") (pintype "passive"))
      (node (ref "U0-C") (pin "24") (pinfunction "PH1_24") (pintype "bidirectional"))
      (node (ref "Y1-C") (pin "1") (pinfunction "1_1") (pintype "passive"))
    )
    (net (code "116") (name "RTS") (class "Default")
      (node (ref "J1-9P") (pin "5") (pinfunction "5_5") (pintype "passive"))
      (node (ref "U0-C") (pin "35") (pinfunction "PA1_35") (pintype "bidirectional"))
    )
    (net (code "117") (name "SCL-1") (class "Default")
      (node (ref "R2-2C") (pin "2") (pinfunction "2_2") (pintype "passive"))
      (node (ref "U0-C") (pin "100") (pinfunction "PA8_100") (pintype "bidirectional"))
      (node (ref "U2-C") (pin "10") (pinfunction "SCL_10") (pintype "bidirectional"))
    )
    (net (code "118") (name "SDA-1") (class "Default")
      (node (ref "R1-2C") (pin "2") (pinfunction "2_2") (pintype "passive"))
      (node (ref "U0-C") (pin "99") (pinfunction "PC9_99") (pintype "bidirectional"))
      (node (ref "U2-C") (pin "9") (pinfunction "SDA_9") (pintype "bidirectional"))
    )
    (net (code "119") (name "SENSE_A") (class "Default")
      (node (ref "R3-5P") (pin "2") (pinfunction "2_2") (pintype "passive"))
      (node (ref "R4-5P") (pin "2") (pinfunction "2_2") (pintype "passive"))
      (node (ref "U0-C") (pin "18") (pinfunction "PF6_18") (pintype "bidirectional"))
      (node (ref "U2-C") (pin "4") (pinfunction "AIN0_4") (pintype "bidirectional"))
    )
    (net (code "120") (name "SENSE_B") (class "Default")
      (node (ref "R7-5P") (pin "2") (pinfunction "2_2") (pintype "passive"))
      (node (ref "R8-5P") (pin "2") (pinfunction "2_2") (pintype "passive"))
      (node (ref "U0-C") (pin "19") (pinfunction "PF7_19") (pintype "bidirectional"))
      (node (ref "U2-C") (pin "5") (pinfunction "AIN1_5") (pintype "bidirectional"))
    )
    (net (code "121") (name "SENSE_C") (class "Default")
      (node (ref "R3-6P") (pin "2") (pinfunction "2_2") (pintype "passive"))
      (node (ref "R4-6P") (pin "2") (pinfunction "2_2") (pintype "passive"))
      (node (ref "U0-C") (pin "20") (pinfunction "PF8_20") (pintype "bidirectional"))
      (node (ref "U2-C") (pin "6") (pinfunction "AIN2_6") (pintype "bidirectional"))
    )
    (net (code "122") (name "SENSE_D") (class "Default")
      (node (ref "R7-6P") (pin "2") (pinfunction "2_2") (pintype "passive"))
      (node (ref "R8-6P") (pin "2") (pinfunction "2_2") (pintype "passive"))
      (node (ref "U0-C") (pin "21") (pinfunction "PF9_21") (pintype "bidirectional"))
      (node (ref "U2-C") (pin "7") (pinfunction "AIN3_7") (pintype "bidirectional"))
    )
    (net (code "123") (name "SENSOR-ERROR") (class "Default")
      (node (ref "D2A-S") (pin "A") (pinfunction "A_A") (pintype "passive"))
      (node (ref "D2B-S") (pin "A") (pinfunction "A_A") (pintype "passive"))
      (node (ref "U0-C") (pin "64") (pinfunction "PE11_64") (pintype "bidirectional"))
    )
    (net (code "124") (name "SENSOR-NOMINAL") (class "Default")
      (node (ref "D1A-S") (pin "A") (pinfunction "A_A") (pintype "passive"))
      (node (ref "D1B-S") (pin "A") (pinfunction "A_A") (pintype "passive"))
      (node (ref "U0-C") (pin "63") (pinfunction "PE10_63") (pintype "bidirectional"))
    )
    (net (code "125") (name "ST") (class "Default")
      (node (ref "U0-C") (pin "69") (pinfunction "PB10_69") (pintype "bidirectional"))
      (node (ref "U2-S") (pin "4") (pinfunction "ST_4") (pintype "bidirectional"))
    )
    (net (code "126") (name "STATUS") (class "Default")
      (node (ref "U0-C") (pin "70") (pinfunction "PB11_70") (pintype "bidirectional"))
      (node (ref "U2-S") (pin "6") (pinfunction "STATUS_6") (pintype "bidirectional"))
    )
    (net (code "127") (name "STORAGE-ERROR") (class "Default")
      (node (ref "D5-C") (pin "A") (pinfunction "A_A") (pintype "passive"))
      (node (ref "U0-C") (pin "58") (pinfunction "PE7_58") (pintype "bidirectional"))
    )
    (net (code "128") (name "SWCLK") (class "Default")
      (node (ref "JP1") (pin "2") (pinfunction "2_2") (pintype "passive"))
      (node (ref "R4-J1C") (pin "1") (pinfunction "1_1") (pintype "passive"))
      (node (ref "R4-J1C") (pin "2") (pinfunction "2_2") (pintype "passive"))
      (node (ref "U0-C") (pin "109") (pinfunction "PA14_109") (pintype "bidirectional"))
    )
    (net (code "129") (name "SWDIO") (class "Default")
      (node (ref "JP1") (pin "3") (pinfunction "3_3") (pintype "passive"))
      (node (ref "R3-J1C") (pin "1") (pinfunction "1_1") (pintype "passive"))
      (node (ref "R3-J1C") (pin "2") (pinfunction "2_2") (pintype "passive"))
      (node (ref "U0-C") (pin "105") (pinfunction "PA13_105") (pintype "bidirectional"))
    )
    (net (code "130") (name "SWO") (class "Default")
      (node (ref "R1-J1C") (pin "2") (pinfunction "2_2") (pintype "passive"))
      (node (ref "U0-C") (pin "133") (pinfunction "PB3_133") (pintype "bidirectional"))
    )
    (net (code "131") (name "U1S-CHECK") (class "Default")
      (node (ref "D2-1S") (pin "A") (pinfunction "A_A") (pintype "passive"))
      (node (ref "U0-C") (pin "65") (pinfunction "PE12_65") (pintype "bidirectional"))
    )
    (net (code "132") (name "U2P-FB") (class "Default")
      (node (ref "C3-2P") (pin "2") (pinfunction "2_2") (pintype "passive"))
      (node (ref "R1-2P") (pin "1") (pinfunction "1_1") (pintype "passive"))
      (node (ref "R2-2P") (pin "2") (pinfunction "2_2") (pintype "passive"))
      (node (ref "U2-P") (pin "15") (pinfunction "FB_15") (pintype "bidirectional"))
    )
    (net (code "133") (name "U2S-CHECK") (class "Default")
      (node (ref "D2-2S") (pin "A") (pinfunction "A_A") (pintype "passive"))
      (node (ref "U0-C") (pin "66") (pinfunction "PE13_66") (pintype "bidirectional"))
    )
    (net (code "135") (name "U3S-CHECK") (class "Default")
      (node (ref "D2-3S") (pin "A") (pinfunction "A_A") (pintype "passive"))
      (node (ref "U0-C") (pin "67") (pinfunction "PE14_67") (pintype "bidirectional"))
    )
    (net (code "137") (name "U4S-CHECK") (class "Default")
      (node (ref "D2-4S") (pin "A") (pinfunction "A_A") (pintype "passive"))
      (node (ref "U0-C") (pin "68") (pinfunction "PE15_68") (pintype "bidirectional"))
    )
    (net (code "138") (name "U9P-FB") (class "Default")
      (node (ref "C1-9P") (pin "2") (pinfunction "2_2") (pintype "passive"))
      (node (ref "C2-9P") (pin "1") (pinfunction "1_1") (pintype "passive"))
      (node (ref "R1-9P") (pin "1") (pinfunction "1_1") (pintype "passive"))
      (node (ref "R2-9P") (pin "2") (pinfunction "2_2") (pintype "passive"))
      (node (ref "U9-P") (pin "4") (pinfunction "FB_4") (pintype "bidirectional"))
    )
    (net (code "139") (name "U9P-SW") (class "Default")
      (node (ref "L1-9P") (pin "1") (pinfunction "1_1") (pintype "bidirectional"))
      (node (ref "U9-P") (pin "5") (pinfunction "SW_5") (pintype "bidirectional"))
    )
    (net (code "140") (name "VBAT") (class "Default")
      (node (ref "1S_LIPO") (pin "1") (pinfunction "1_1") (pintype "bidirectional"))
      (node (ref "C2-1P") (pin "1") (pinfunction "1_1") (pintype "passive"))
      (node (ref "D1-11P") (pin "2") (pinfunction "A_2") (pintype "bidirectional"))
      (node (ref "J2-CHARGETERMINAL") (pin "1") (pinfunction "1_1") (pintype "bidirectional"))
      (node (ref "J2-CHARGETERMINAL") (pin "3") (pinfunction "3_3") (pintype "bidirectional"))
      (node (ref "J2-CHARGETERMINAL") (pin "5") (pinfunction "5_5") (pintype "bidirectional"))
      (node (ref "J2-CHARGETERMINAL") (pin "7") (pinfunction "7_7") (pintype "bidirectional"))
      (node (ref "R4-11P") (pin "1") (pinfunction "1_1") (pintype "passive"))
      (node (ref "U1-P") (pin "3") (pinfunction "VBAT_3") (pintype "bidirectional"))
    )
    (net (code "141") (name "VDDA") (class "Default")
      (node (ref "FB1-0C") (pin "2") (pinfunction "2_2") (pintype "bidirectional"))
      (node (ref "U0-C") (pin "32") (pinfunction "VREF+_32") (pintype "input"))
      (node (ref "U0-C") (pin "33") (pinfunction "VDDA_33") (pintype "power_in"))
    )
    (net (code "142") (name "VUSB") (class "Default")
      (node (ref "C1-1P") (pin "1") (pinfunction "1_1") (pintype "passive"))
      (node (ref "D1-1P") (pin "A") (pinfunction "A_A") (pintype "passive"))
      (node (ref "J2-C") (pin "1") (pinfunction "VBUS_1") (pintype "power_in"))
      (node (ref "U1-P") (pin "4") (pinfunction "VDD_4") (pintype "power_in"))
    )
    (net (code "143") (name "V_LDO_IN") (class "Default")
      (node (ref "C1-11P") (pin "1") (pinfunction "1_1") (pintype "passive"))
      (node (ref "C1-2P") (pin "1") (pinfunction "1_1") (pintype "passive"))
      (node (ref "C2-2P") (pin "1") (pinfunction "1_1") (pintype "passive"))
      (node (ref "D1-11P") (pin "1") (pinfunction "K_1") (pintype "bidirectional"))
      (node (ref "R1-11P") (pin "2") (pinfunction "2_2") (pintype "passive"))
      (node (ref "U2-P") (pin "10") (pinfunction "VIN_10") (pintype "bidirectional"))
      (node (ref "U2-P") (pin "11") (pinfunction "EN_11") (pintype "bidirectional"))
      (node (ref "U2-P") (pin "6") (pinfunction "PVIN_1_6") (pintype "bidirectional"))
      (node (ref "U2-P") (pin "7") (pinfunction "PVIN_2_7") (pintype "bidirectional"))
      (node (ref "U2-P") (pin "8") (pinfunction "PVIN_3_8") (pintype "bidirectional"))
      (node (ref "U2-P") (pin "9") (pinfunction "PVIN_4_9") (pintype "bidirectional"))
    )
    (net (code "144") (name "WP") (class "Default")
      (node (ref "U0-C") (pin "78") (pinfunction "PD9_78") (pintype "bidirectional"))
      (node (ref "U1-C") (pin "3") (pinfunction "~{WP}/IO2_3") (pintype "bidirectional"))
    )
    (net (code "145") (name "unconnected-(J1-9P-Pad1)") (class "Default")
      (node (ref "J1-9P") (pin "1") (pinfunction "1_1") (pintype "passive"))
    )
    (net (code "146") (name "unconnected-(J1-9P-Pad2)") (class "Default")
      (node (ref "J1-9P") (pin "2") (pinfunction "2_2") (pintype "passive"))
    )
    (net (code "147") (name "unconnected-(J1-9P-Pad3)") (class "Default")
      (node (ref "J1-9P") (pin "3") (pinfunction "3_3") (pintype "passive"))
    )
    (net (code "148") (name "unconnected-(J1-9P-Pad4)") (class "Default")
      (node (ref "J1-9P") (pin "4") (pinfunction "4_4") (pintype "passive"))
    )
    (net (code "149") (name "unconnected-(J1-9P-Pad6)") (class "Default")
      (node (ref "J1-9P") (pin "6") (pinfunction "6_6") (pintype "passive"))
    )
    (net (code "150") (name "unconnected-(J1-9P-Pad8)") (class "Default")
      (node (ref "J1-9P") (pin "8") (pinfunction "8_8") (pintype "passive"))
    )
    (net (code "151") (name "unconnected-(J1-9P-Pad10)") (class "Default")
      (node (ref "J1-9P") (pin "10") (pinfunction "10_10") (pintype "passive"))
    )
    (net (code "152") (name "unconnected-(J1-9P-Pad11)") (class "Default")
      (node (ref "J1-9P") (pin "11") (pinfunction "11_11") (pintype "passive"))
    )
    (net (code "153") (name "unconnected-(J1-9P-Pad12)") (class "Default")
      (node (ref "J1-9P") (pin "12") (pinfunction "12_12") (pintype "passive"))
    )
    (net (code "154") (name "unconnected-(J1-9P-Pad16)") (class "Default")
      (node (ref "J1-9P") (pin "16") (pinfunction "16_16") (pintype "passive"))
    )
    (net (code "155") (name "unconnected-(Q1-C-Pad2)") (class "Default")
      (node (ref "Q1") (pin "2") (pinfunction "C_2") (pintype "passive"))
    )
    (net (code "156") (name "unconnected-(Q1-E-Pad3)") (class "Default")
      (node (ref "Q1") (pin "3") (pinfunction "E_3") (pintype "passive"))
    )
    (net (code "157") (name "unconnected-(R1-Pad1)") (class "Default")
      (node (ref "R1") (pin "1") (pinfunction "1_1") (pintype "passive"))
    )
    (net (code "158") (name "unconnected-(R1-Pad2)") (class "Default")
      (node (ref "R1") (pin "2") (pinfunction "2_2") (pintype "passive"))
    )
    (net (code "159") (name "unconnected-(R2-Pad1)") (class "Default")
      (node (ref "R2") (pin "1") (pinfunction "1_1") (pintype "passive"))
    )
    (net (code "160") (name "unconnected-(R3-Pad1)") (class "Default")
      (node (ref "R3") (pin "1") (pinfunction "1_1") (pintype "passive"))
    )
    (net (code "161") (name "unconnected-(R3-Pad2)") (class "Default")
      (node (ref "R3") (pin "2") (pinfunction "2_2") (pintype "passive"))
    )
    (net (code "162") (name "unconnected-(S0-0C-P1-Pad4)") (class "Default")
      (node (ref "S0-0C") (pin "4") (pinfunction "P1_4") (pintype "passive"))
    )
    (net (code "163") (name "unconnected-(S0-0C-S1-Pad2)") (class "Default")
      (node (ref "S0-0C") (pin "2") (pinfunction "S1_2") (pintype "passive"))
    )
    (net (code "164") (name "unconnected-(U$2-PadV+)") (class "Default")
      (node (ref "U$2") (pin "V+") (pinfunction "V+_V+") (pintype "bidirectional"))
    )
    (net (code "165") (name "unconnected-(U$2-PadV-)") (class "Default")
      (node (ref "U$2") (pin "V-") (pinfunction "V-_V-") (pintype "bidirectional"))
    )
    (net (code "166") (name "unconnected-(U0-C-PA4-Pad40)") (class "Default")
      (node (ref "U0-C") (pin "40") (pinfunction "PA4_40") (pintype "bidirectional"))
    )
    (net (code "167") (name "unconnected-(U0-C-PA9-Pad101)") (class "Default")
      (node (ref "U0-C") (pin "101") (pinfunction "PA9_101") (pintype "bidirectional"))
    )
    (net (code "168") (name "unconnected-(U0-C-PA15-Pad110)") (class "Default")
      (node (ref "U0-C") (pin "110") (pinfunction "PA15_110") (pintype "bidirectional"))
    )
    (net (code "169") (name "unconnected-(U0-C-PB2-Pad48)") (class "Default")
      (node (ref "U0-C") (pin "48") (pinfunction "PB2_48") (pintype "bidirectional"))
    )
    (net (code "170") (name "unconnected-(U0-C-PB4-Pad134)") (class "Default")
      (node (ref "U0-C") (pin "134") (pinfunction "PB4_134") (pintype "bidirectional"))
    )
    (net (code "171") (name "unconnected-(U0-C-PB5-Pad135)") (class "Default")
      (node (ref "U0-C") (pin "135") (pinfunction "PB5_135") (pintype "bidirectional"))
    )
    (net (code "172") (name "unconnected-(U0-C-PB6-Pad136)") (class "Default")
      (node (ref "U0-C") (pin "136") (pinfunction "PB6_136") (pintype "bidirectional"))
    )
    (net (code "173") (name "unconnected-(U0-C-PB7-Pad137)") (class "Default")
      (node (ref "U0-C") (pin "137") (pinfunction "PB7_137") (pintype "bidirectional"))
    )
    (net (code "174") (name "unconnected-(U0-C-PB8-Pad139)") (class "Default")
      (node (ref "U0-C") (pin "139") (pinfunction "PB8_139") (pintype "bidirectional"))
    )
    (net (code "175") (name "unconnected-(U0-C-PB9-Pad140)") (class "Default")
      (node (ref "U0-C") (pin "140") (pinfunction "PB9_140") (pintype "bidirectional"))
    )
    (net (code "176") (name "unconnected-(U0-C-PB12-Pad73)") (class "Default")
      (node (ref "U0-C") (pin "73") (pinfunction "PB12_73") (pintype "bidirectional"))
    )
    (net (code "177") (name "unconnected-(U0-C-PB13-Pad74)") (class "Default")
      (node (ref "U0-C") (pin "74") (pinfunction "PB13_74") (pintype "bidirectional"))
    )
    (net (code "178") (name "unconnected-(U0-C-PB14-Pad75)") (class "Default")
      (node (ref "U0-C") (pin "75") (pinfunction "PB14_75") (pintype "bidirectional"))
    )
    (net (code "179") (name "unconnected-(U0-C-PB15-Pad76)") (class "Default")
      (node (ref "U0-C") (pin "76") (pinfunction "PB15_76") (pintype "bidirectional"))
    )
    (net (code "180") (name "unconnected-(U0-C-PC0-Pad26)") (class "Default")
      (node (ref "U0-C") (pin "26") (pinfunction "PC0_26") (pintype "bidirectional"))
    )
    (net (code "181") (name "unconnected-(U0-C-PC1-Pad27)") (class "Default")
      (node (ref "U0-C") (pin "27") (pinfunction "PC1_27") (pintype "bidirectional"))
    )
    (net (code "182") (name "unconnected-(U0-C-PC2-Pad28)") (class "Default")
      (node (ref "U0-C") (pin "28") (pinfunction "PC2_28") (pintype "bidirectional"))
    )
    (net (code "183") (name "unconnected-(U0-C-PC3-Pad29)") (class "Default")
      (node (ref "U0-C") (pin "29") (pinfunction "PC3_29") (pintype "bidirectional"))
    )
    (net (code "184") (name "unconnected-(U0-C-PC13-Pad7)") (class "Default")
      (node (ref "U0-C") (pin "7") (pinfunction "PC13_7") (pintype "bidirectional"))
    )
    (net (code "185") (name "unconnected-(U0-C-PC14-Pad8)") (class "Default")
      (node (ref "U0-C") (pin "8") (pinfunction "PC14_8") (pintype "bidirectional"))
    )
    (net (code "186") (name "unconnected-(U0-C-PC15-Pad9)") (class "Default")
      (node (ref "U0-C") (pin "9") (pinfunction "PC15_9") (pintype "bidirectional"))
    )
    (net (code "187") (name "unconnected-(U0-C-PD1-Pad115)") (class "Default")
      (node (ref "U0-C") (pin "115") (pinfunction "PD1_115") (pintype "bidirectional"))
    )
    (net (code "188") (name "unconnected-(U0-C-PD2-Pad116)") (class "Default")
      (node (ref "U0-C") (pin "116") (pinfunction "PD2_116") (pintype "bidirectional"))
    )
    (net (code "189") (name "unconnected-(U0-C-PD3-Pad117)") (class "Default")
      (node (ref "U0-C") (pin "117") (pinfunction "PD3_117") (pintype "bidirectional"))
    )
    (net (code "190") (name "unconnected-(U0-C-PD4-Pad118)") (class "Default")
      (node (ref "U0-C") (pin "118") (pinfunction "PD4_118") (pintype "bidirectional"))
    )
    (net (code "191") (name "unconnected-(U0-C-PD5-Pad119)") (class "Default")
      (node (ref "U0-C") (pin "119") (pinfunction "PD5_119") (pintype "bidirectional"))
    )
    (net (code "192") (name "unconnected-(U0-C-PD6-Pad122)") (class "Default")
      (node (ref "U0-C") (pin "122") (pinfunction "PD6_122") (pintype "bidirectional"))
    )
    (net (code "193") (name "unconnected-(U0-C-PD7-Pad123)") (class "Default")
      (node (ref "U0-C") (pin "123") (pinfunction "PD7_123") (pintype "bidirectional"))
    )
    (net (code "194") (name "unconnected-(U0-C-PD10-Pad79)") (class "Default")
      (node (ref "U0-C") (pin "79") (pinfunction "PD10_79") (pintype "bidirectional"))
    )
    (net (code "195") (name "unconnected-(U0-C-PD11-Pad80)") (class "Default")
      (node (ref "U0-C") (pin "80") (pinfunction "PD11_80") (pintype "bidirectional"))
    )
    (net (code "196") (name "unconnected-(U0-C-PD12-Pad81)") (class "Default")
      (node (ref "U0-C") (pin "81") (pinfunction "PD12_81") (pintype "bidirectional"))
    )
    (net (code "197") (name "unconnected-(U0-C-PD13-Pad82)") (class "Default")
      (node (ref "U0-C") (pin "82") (pinfunction "PD13_82") (pintype "bidirectional"))
    )
    (net (code "198") (name "unconnected-(U0-C-PD14-Pad85)") (class "Default")
      (node (ref "U0-C") (pin "85") (pinfunction "PD14_85") (pintype "bidirectional"))
    )
    (net (code "199") (name "unconnected-(U0-C-PD15-Pad86)") (class "Default")
      (node (ref "U0-C") (pin "86") (pinfunction "PD15_86") (pintype "bidirectional"))
    )
    (net (code "200") (name "unconnected-(U0-C-PE0-Pad141)") (class "Default")
      (node (ref "U0-C") (pin "141") (pinfunction "PE0_141") (pintype "bidirectional"))
    )
    (net (code "201") (name "unconnected-(U0-C-PE1-Pad142)") (class "Default")
      (node (ref "U0-C") (pin "142") (pinfunction "PE1_142") (pintype "bidirectional"))
    )
    (net (code "202") (name "unconnected-(U0-C-PE2-Pad1)") (class "Default")
      (node (ref "U0-C") (pin "1") (pinfunction "PE2_1") (pintype "bidirectional"))
    )
    (net (code "203") (name "unconnected-(U0-C-PE3-Pad2)") (class "Default")
      (node (ref "U0-C") (pin "2") (pinfunction "PE3_2") (pintype "bidirectional"))
    )
    (net (code "204") (name "unconnected-(U0-C-PE4-Pad3)") (class "Default")
      (node (ref "U0-C") (pin "3") (pinfunction "PE4_3") (pintype "bidirectional"))
    )
    (net (code "205") (name "unconnected-(U0-C-PE5-Pad4)") (class "Default")
      (node (ref "U0-C") (pin "4") (pinfunction "PE5_4") (pintype "bidirectional"))
    )
    (net (code "206") (name "unconnected-(U0-C-PE6-Pad5)") (class "Default")
      (node (ref "U0-C") (pin "5") (pinfunction "PE6_5") (pintype "bidirectional"))
    )
    (net (code "207") (name "unconnected-(U0-C-PE9-Pad60)") (class "Default")
      (node (ref "U0-C") (pin "60") (pinfunction "PE9_60") (pintype "bidirectional"))
    )
    (net (code "208") (name "unconnected-(U0-C-PF0-Pad10)") (class "Default")
      (node (ref "U0-C") (pin "10") (pinfunction "PF0_10") (pintype "bidirectional"))
    )
    (net (code "209") (name "unconnected-(U0-C-PF5-Pad15)") (class "Default")
      (node (ref "U0-C") (pin "15") (pinfunction "PF5_15") (pintype "bidirectional"))
    )
    (net (code "210") (name "unconnected-(U0-C-PF10-Pad22)") (class "Default")
      (node (ref "U0-C") (pin "22") (pinfunction "PF10_22") (pintype "bidirectional"))
    )
    (net (code "211") (name "unconnected-(U0-C-PF11-Pad49)") (class "Default")
      (node (ref "U0-C") (pin "49") (pinfunction "PF11_49") (pintype "bidirectional"))
    )
    (net (code "212") (name "unconnected-(U0-C-PF12-Pad50)") (class "Default")
      (node (ref "U0-C") (pin "50") (pinfunction "PF12_50") (pintype "bidirectional"))
    )
    (net (code "213") (name "unconnected-(U0-C-PG2-Pad87)") (class "Default")
      (node (ref "U0-C") (pin "87") (pinfunction "PG2_87") (pintype "bidirectional"))
    )
    (net (code "214") (name "unconnected-(U0-C-PG3-Pad88)") (class "Default")
      (node (ref "U0-C") (pin "88") (pinfunction "PG3_88") (pintype "bidirectional"))
    )
    (net (code "215") (name "unconnected-(U0-C-PG5-Pad90)") (class "Default")
      (node (ref "U0-C") (pin "90") (pinfunction "PG5_90") (pintype "bidirectional"))
    )
    (net (code "216") (name "unconnected-(U0-C-PG6-Pad91)") (class "Default")
      (node (ref "U0-C") (pin "91") (pinfunction "PG6_91") (pintype "bidirectional"))
    )
    (net (code "217") (name "unconnected-(U0-C-PG7-Pad92)") (class "Default")
      (node (ref "U0-C") (pin "92") (pinfunction "PG7_92") (pintype "bidirectional"))
    )
    (net (code "218") (name "unconnected-(U0-C-PG8-Pad93)") (class "Default")
      (node (ref "U0-C") (pin "93") (pinfunction "PG8_93") (pintype "bidirectional"))
    )
    (net (code "219") (name "unconnected-(U0-C-PG9-Pad124)") (class "Default")
      (node (ref "U0-C") (pin "124") (pinfunction "PG9_124") (pintype "bidirectional"))
    )
    (net (code "220") (name "unconnected-(U0-C-PG10-Pad125)") (class "Default")
      (node (ref "U0-C") (pin "125") (pinfunction "PG10_125") (pintype "bidirectional"))
    )
    (net (code "221") (name "unconnected-(U0-C-PG11-Pad126)") (class "Default")
      (node (ref "U0-C") (pin "126") (pinfunction "PG11_126") (pintype "bidirectional"))
    )
    (net (code "222") (name "unconnected-(U0-C-PG12-Pad127)") (class "Default")
      (node (ref "U0-C") (pin "127") (pinfunction "PG12_127") (pintype "bidirectional"))
    )
    (net (code "223") (name "unconnected-(U0-C-PG13-Pad128)") (class "Default")
      (node (ref "U0-C") (pin "128") (pinfunction "PG13_128") (pintype "bidirectional"))
    )
    (net (code "224") (name "unconnected-(U0-C-PG14-Pad129)") (class "Default")
      (node (ref "U0-C") (pin "129") (pinfunction "PG14_129") (pintype "bidirectional"))
    )
    (net (code "225") (name "unconnected-(U0-C-PG15-Pad132)") (class "Default")
      (node (ref "U0-C") (pin "132") (pinfunction "PG15_132") (pintype "bidirectional"))
    )
    (net (code "226") (name "unconnected-(U1-C-EP-Pad9)") (class "Default")
      (node (ref "U1-C") (pin "9") (pinfunction "EP_9") (pintype "bidirectional"))
    )
    (net (code "227") (name "unconnected-(U1-S-AUX_CL-Pad7)") (class "Default")
      (node (ref "U1-S") (pin "7") (pinfunction "AUX_CL_7") (pintype "bidirectional"))
    )
    (net (code "228") (name "unconnected-(U1-S-AUX_DA-Pad21)") (class "Default")
      (node (ref "U1-S") (pin "21") (pinfunction "AUX_DA_21") (pintype "bidirectional"))
    )
    (net (code "229") (name "unconnected-(U1-S-FSYNC-Pad11)") (class "Default")
      (node (ref "U1-S") (pin "11") (pinfunction "FSYNC_11") (pintype "bidirectional"))
    )
    (net (code "230") (name "unconnected-(U1-S-INT1-Pad12)") (class "Default")
      (node (ref "U1-S") (pin "12") (pinfunction "INT1_12") (pintype "bidirectional"))
    )
    (net (code "231") (name "unconnected-(U1-S-NC.1-Pad1)") (class "Default")
      (node (ref "U1-S") (pin "1") (pinfunction "NC.1_1") (pintype "bidirectional"))
    )
    (net (code "232") (name "unconnected-(U1-S-NC.2-Pad2)") (class "Default")
      (node (ref "U1-S") (pin "2") (pinfunction "NC.2_2") (pintype "bidirectional"))
    )
    (net (code "233") (name "unconnected-(U1-S-NC.3-Pad3)") (class "Default")
      (node (ref "U1-S") (pin "3") (pinfunction "NC.3_3") (pintype "bidirectional"))
    )
    (net (code "234") (name "unconnected-(U1-S-NC.4-Pad4)") (class "Default")
      (node (ref "U1-S") (pin "4") (pinfunction "NC.4_4") (pintype "bidirectional"))
    )
    (net (code "235") (name "unconnected-(U1-S-NC.5-Pad5)") (class "Default")
      (node (ref "U1-S") (pin "5") (pinfunction "NC.5_5") (pintype "bidirectional"))
    )
    (net (code "236") (name "unconnected-(U1-S-NC.6-Pad6)") (class "Default")
      (node (ref "U1-S") (pin "6") (pinfunction "NC.6_6") (pintype "bidirectional"))
    )
    (net (code "237") (name "unconnected-(U1-S-NC.14-Pad14)") (class "Default")
      (node (ref "U1-S") (pin "14") (pinfunction "NC.14_14") (pintype "bidirectional"))
    )
    (net (code "238") (name "unconnected-(U1-S-NC.15-Pad15)") (class "Default")
      (node (ref "U1-S") (pin "15") (pinfunction "NC.15_15") (pintype "bidirectional"))
    )
    (net (code "239") (name "unconnected-(U1-S-NC.16-Pad16)") (class "Default")
      (node (ref "U1-S") (pin "16") (pinfunction "NC.16_16") (pintype "bidirectional"))
    )
    (net (code "240") (name "unconnected-(U1-S-NC.17-Pad17)") (class "Default")
      (node (ref "U1-S") (pin "17") (pinfunction "NC.17_17") (pintype "bidirectional"))
    )
    (net (code "241") (name "unconnected-(U1-S-RESV.NC-Pad19)") (class "Default")
      (node (ref "U1-S") (pin "19") (pinfunction "RESV.NC_19") (pintype "bidirectional"))
    )
    (net (code "242") (name "unconnected-(U2-P-EP-Pad21)") (class "Default")
      (node (ref "U2-P") (pin "21") (pinfunction "EP_21") (pintype "bidirectional"))
    )
    (net (code "243") (name "unconnected-(U2-P-LX1_2-Pad5)") (class "Default")
      (node (ref "U2-P") (pin "5") (pinfunction "LX1_2_5") (pintype "bidirectional"))
    )
    (net (code "244") (name "unconnected-(U2-P-LX2_2-Pad2)") (class "Default")
      (node (ref "U2-P") (pin "2") (pinfunction "LX2_2_2") (pintype "bidirectional"))
    )
    (net (code "245") (name "unconnected-(U2-P-NC-Pad16)") (class "Default")
      (node (ref "U2-P") (pin "16") (pinfunction "NC_16") (pintype "no_connect"))
    )
    (net (code "246") (name "unconnected-(U2-P-SGND_2-Pad14)") (class "Default")
      (node (ref "U2-P") (pin "14") (pinfunction "SGND_2_14") (pintype "bidirectional"))
    )
    (net (code "247") (name "unconnected-(U4-S-1PPS-Pad13)") (class "Default")
      (node (ref "U4-S") (pin "13") (pinfunction "1PPS_13") (pintype "bidirectional"))
    )
    (net (code "248") (name "unconnected-(U4-S-NREST-Pad2)") (class "Default")
      (node (ref "U4-S") (pin "2") (pinfunction "NREST_2") (pintype "bidirectional"))
    )
    (net (code "249") (name "unconnected-(U4-S-RTCM-Pad14)") (class "Default")
      (node (ref "U4-S") (pin "14") (pinfunction "RTCM_14") (pintype "bidirectional"))
    )
    (net (code "250") (name "unconnected-(U4-S-VBACKUP-Pad4)") (class "Default")
      (node (ref "U4-S") (pin "4") (pinfunction "VBACKUP_4") (pintype "bidirectional"))
    )
  )
)
